# homeboard24.net
KiCad netlist of a schematic drawn in EAGLE
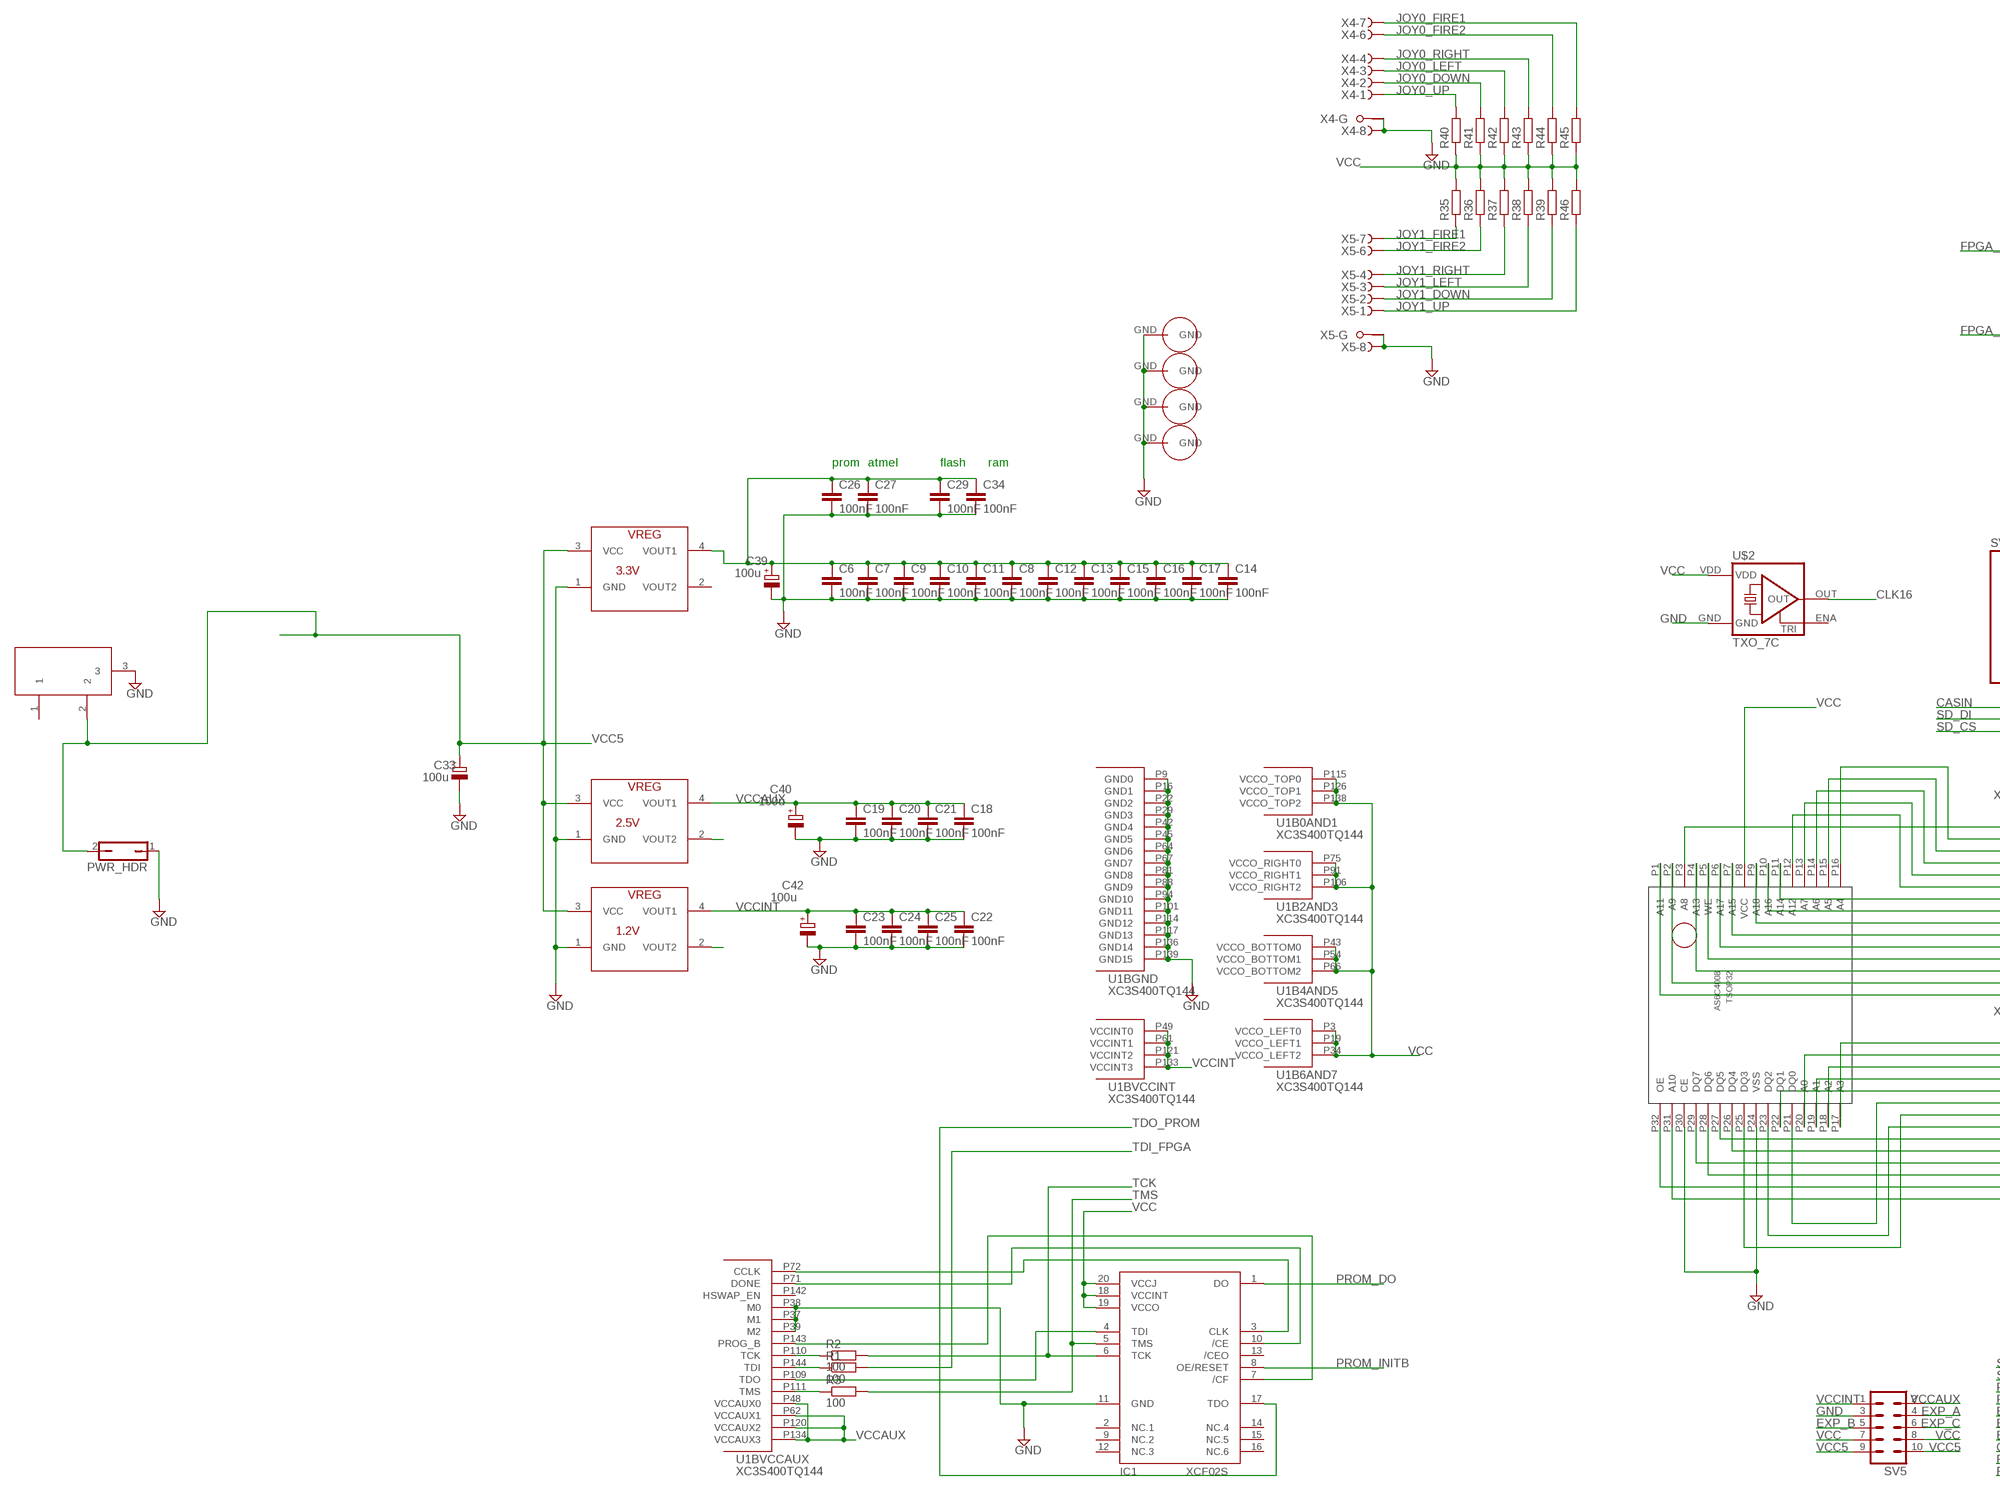
[diagram p0: schematic, sheet 1, part 1 of 3]
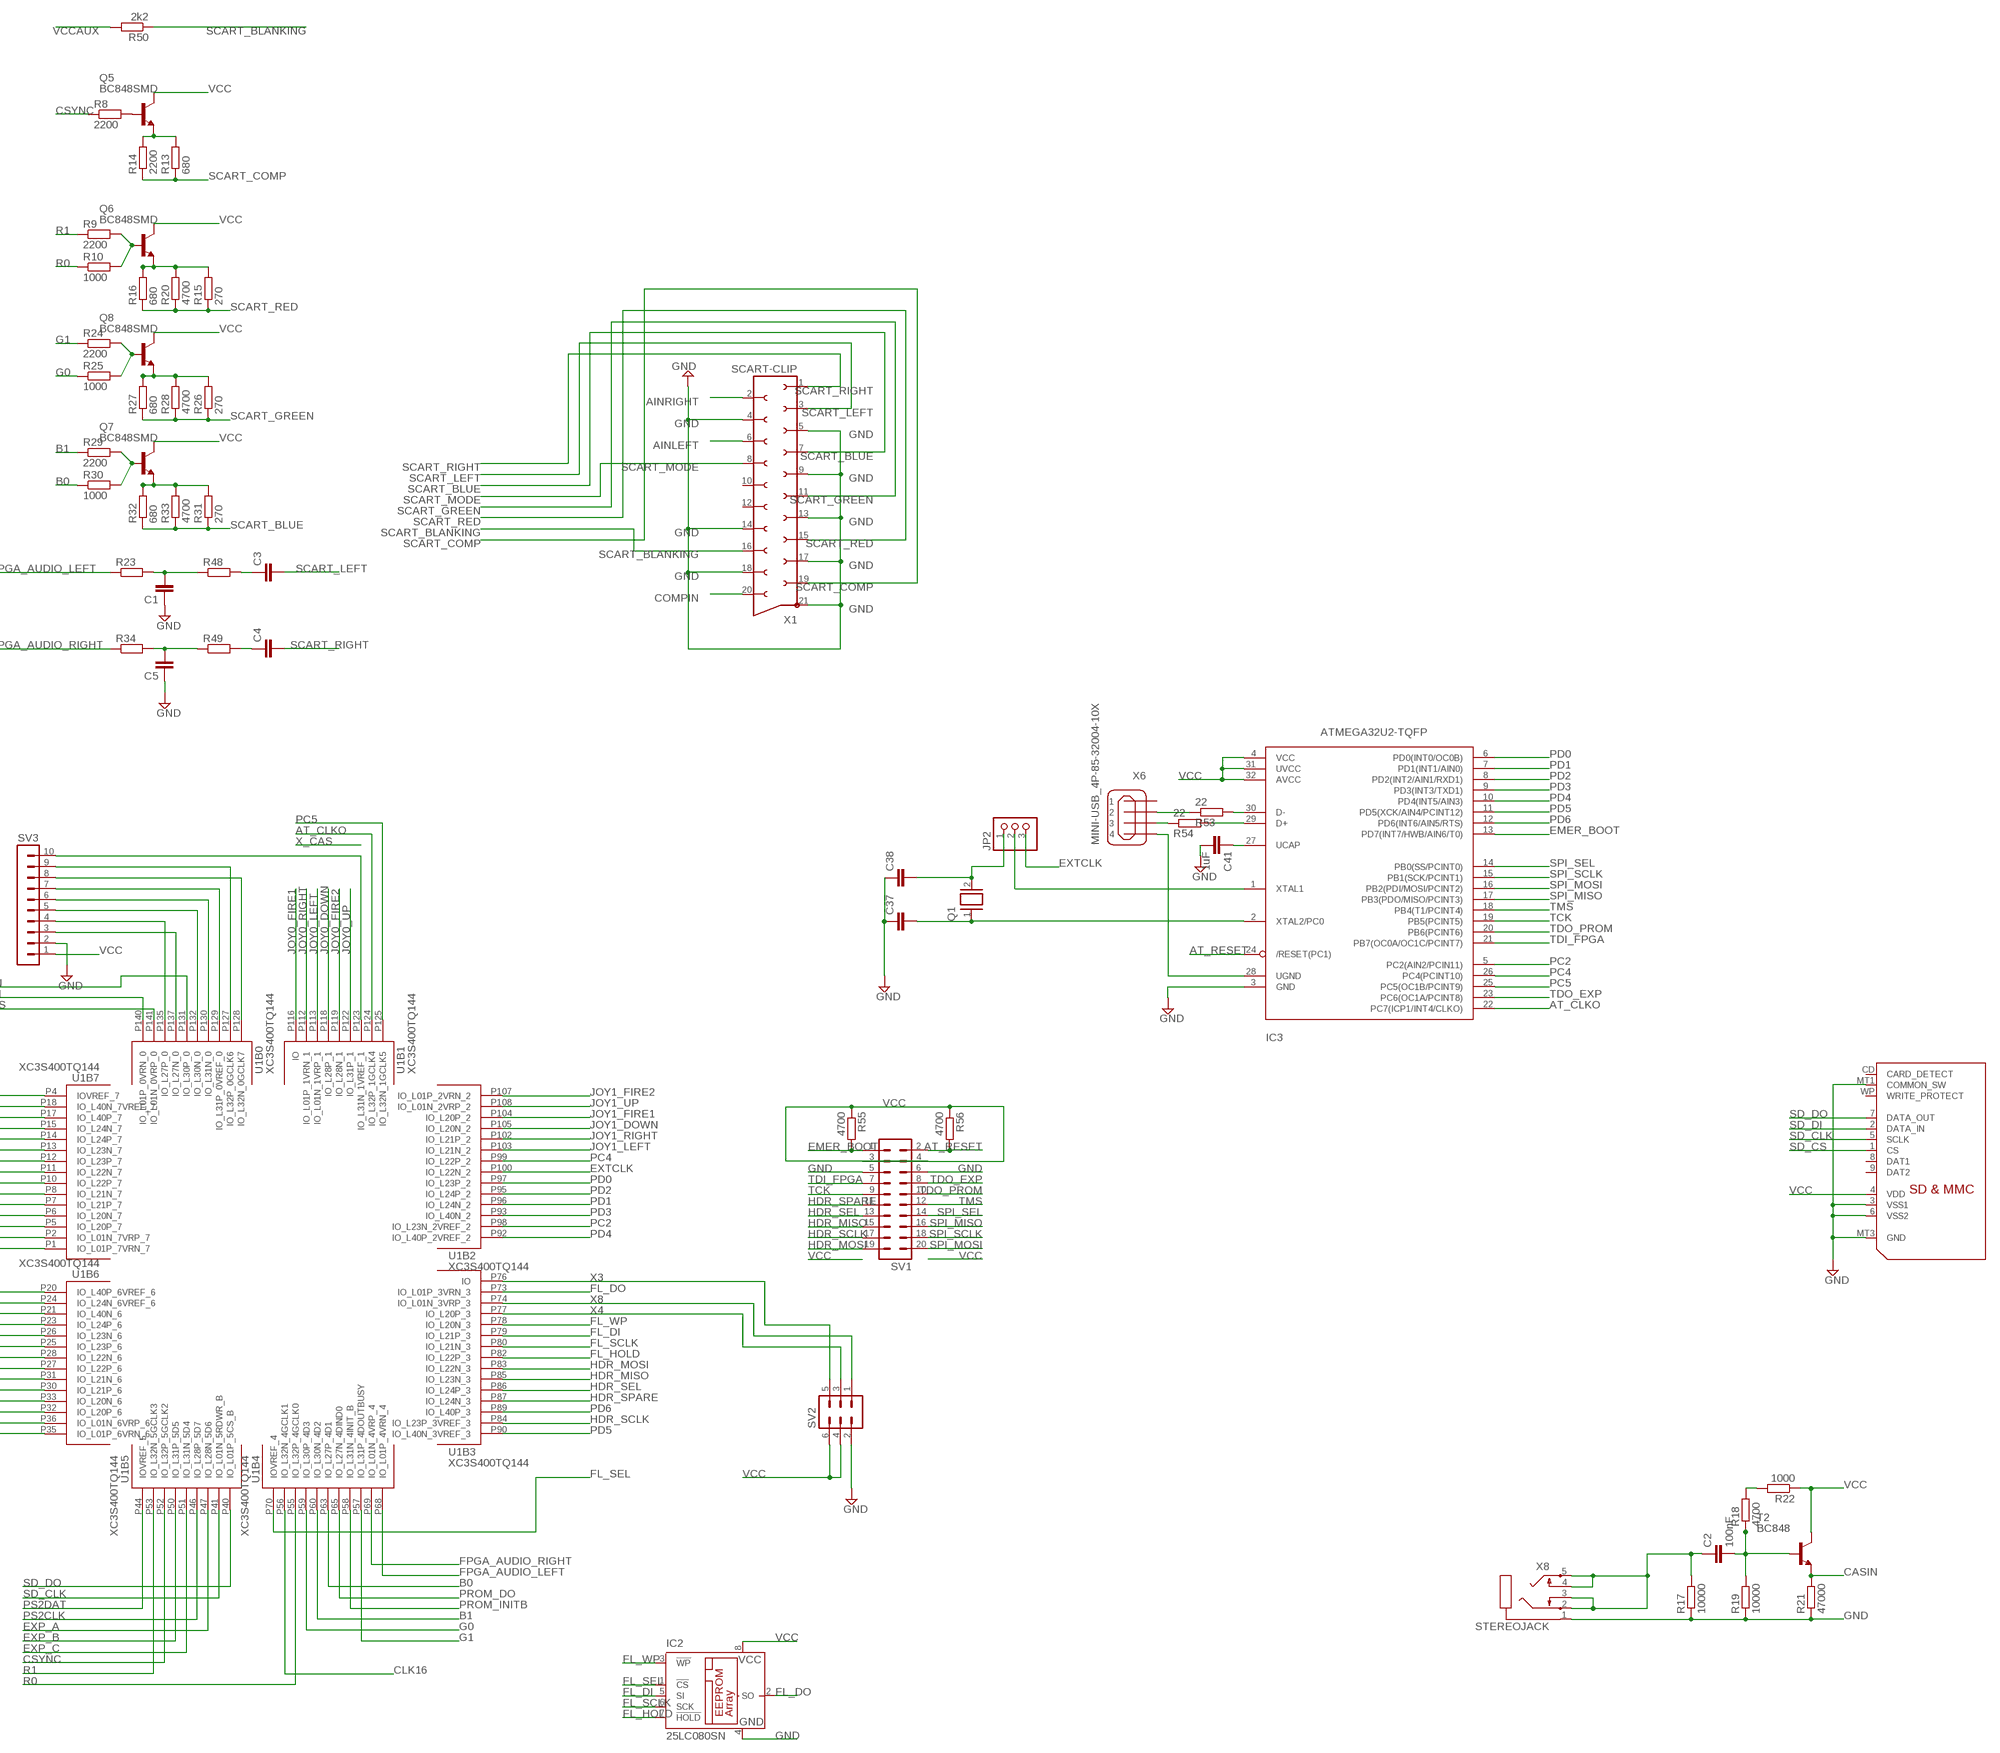
[diagram p1: schematic, sheet 1, part 2 of 3]
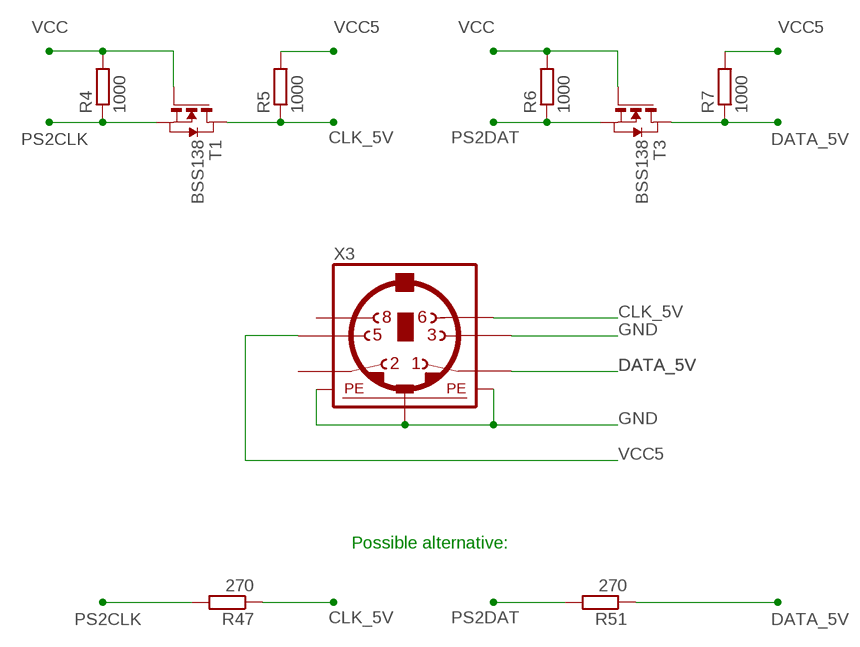
[diagram p2: schematic, sheet 1, part 3 of 3]

(export (version "E")
  (design (tool "Eeschema 10.0.6"))
  (components
    (comp (ref "C1")
      (value "C-EUC0603")
      (footprint "eagle-import:C0603")
      (libsource (lib "eagle-import") (part "resistor_C-EUC0603"))
    )
    (comp (ref "C2")
      (value "100nF")
      (footprint "eagle-import:C0603")
      (libsource (lib "eagle-import") (part "resistor_C-EUC0603"))
    )
    (comp (ref "C3")
      (value "C-EUC0603")
      (footprint "eagle-import:C0603")
      (libsource (lib "eagle-import") (part "resistor_C-EUC0603"))
    )
    (comp (ref "C4")
      (value "C-EUC0603")
      (footprint "eagle-import:C0603")
      (libsource (lib "eagle-import") (part "resistor_C-EUC0603"))
    )
    (comp (ref "C5")
      (value "C-EUC0603")
      (footprint "eagle-import:C0603")
      (libsource (lib "eagle-import") (part "resistor_C-EUC0603"))
    )
    (comp (ref "C6")
      (value "100nF")
      (footprint "eagle-import:C0603")
      (libsource (lib "eagle-import") (part "C-EUC0603"))
    )
    (comp (ref "C7")
      (value "100nF")
      (footprint "eagle-import:C0603")
      (libsource (lib "eagle-import") (part "C-EUC0603"))
    )
    (comp (ref "C8")
      (value "100nF")
      (footprint "eagle-import:C0603")
      (libsource (lib "eagle-import") (part "C-EUC0603"))
    )
    (comp (ref "C9")
      (value "100nF")
      (footprint "eagle-import:C0603")
      (libsource (lib "eagle-import") (part "C-EUC0603"))
    )
    (comp (ref "C10")
      (value "100nF")
      (footprint "eagle-import:C0603")
      (libsource (lib "eagle-import") (part "C-EUC0603"))
    )
    (comp (ref "C11")
      (value "100nF")
      (footprint "eagle-import:C0603")
      (libsource (lib "eagle-import") (part "C-EUC0603"))
    )
    (comp (ref "C12")
      (value "100nF")
      (footprint "eagle-import:C0603")
      (libsource (lib "eagle-import") (part "C-EUC0603"))
    )
    (comp (ref "C13")
      (value "100nF")
      (footprint "eagle-import:C0603")
      (libsource (lib "eagle-import") (part "C-EUC0603"))
    )
    (comp (ref "C14")
      (value "100nF")
      (footprint "eagle-import:C0603")
      (libsource (lib "eagle-import") (part "C-EUC0603"))
    )
    (comp (ref "C15")
      (value "100nF")
      (footprint "eagle-import:C0603")
      (libsource (lib "eagle-import") (part "C-EUC0603"))
    )
    (comp (ref "C16")
      (value "100nF")
      (footprint "eagle-import:C0603")
      (libsource (lib "eagle-import") (part "C-EUC0603"))
    )
    (comp (ref "C17")
      (value "100nF")
      (footprint "eagle-import:C0603")
      (libsource (lib "eagle-import") (part "C-EUC0603"))
    )
    (comp (ref "C18")
      (value "100nF")
      (footprint "eagle-import:C0603")
      (libsource (lib "eagle-import") (part "C-EUC0603"))
    )
    (comp (ref "C19")
      (value "100nF")
      (footprint "eagle-import:C0603")
      (libsource (lib "eagle-import") (part "C-EUC0603"))
    )
    (comp (ref "C20")
      (value "100nF")
      (footprint "eagle-import:C0603")
      (libsource (lib "eagle-import") (part "C-EUC0603"))
    )
    (comp (ref "C21")
      (value "100nF")
      (footprint "eagle-import:C0603")
      (libsource (lib "eagle-import") (part "C-EUC0603"))
    )
    (comp (ref "C22")
      (value "100nF")
      (footprint "eagle-import:C0603")
      (libsource (lib "eagle-import") (part "C-EUC0603"))
    )
    (comp (ref "C23")
      (value "100nF")
      (footprint "eagle-import:C0603")
      (libsource (lib "eagle-import") (part "C-EUC0603"))
    )
    (comp (ref "C24")
      (value "100nF")
      (footprint "eagle-import:C0603")
      (libsource (lib "eagle-import") (part "C-EUC0603"))
    )
    (comp (ref "C25")
      (value "100nF")
      (footprint "eagle-import:C0603")
      (libsource (lib "eagle-import") (part "C-EUC0603"))
    )
    (comp (ref "C26")
      (value "100nF")
      (footprint "eagle-import:C0603")
      (libsource (lib "eagle-import") (part "C-EUC0603"))
    )
    (comp (ref "C27")
      (value "100nF")
      (footprint "eagle-import:C0603")
      (libsource (lib "eagle-import") (part "C-EUC0603"))
    )
    (comp (ref "C29")
      (value "100nF")
      (footprint "eagle-import:C0603")
      (libsource (lib "eagle-import") (part "C-EUC0603"))
    )
    (comp (ref "C33")
      (value "100u")
      (footprint "eagle-import:PANASONIC_D")
      (libsource (lib "eagle-import") (part "CPOL-EUD"))
    )
    (comp (ref "C34")
      (value "100nF")
      (footprint "eagle-import:C0603")
      (libsource (lib "eagle-import") (part "C-EUC0603"))
    )
    (comp (ref "C37")
      (value "C-EUC0805")
      (footprint "eagle-import:C0805")
      (libsource (lib "eagle-import") (part "C-EUC0805"))
    )
    (comp (ref "C38")
      (value "C-EUC0805")
      (footprint "eagle-import:C0805")
      (libsource (lib "eagle-import") (part "C-EUC0805"))
    )
    (comp (ref "C39")
      (value "100u")
      (footprint "eagle-import:PANASONIC_D")
      (libsource (lib "eagle-import") (part "CPOL-EUD"))
    )
    (comp (ref "C40")
      (value "100u")
      (footprint "eagle-import:PANASONIC_D")
      (libsource (lib "eagle-import") (part "CPOL-EUD"))
    )
    (comp (ref "C41")
      (value "1uF")
      (footprint "eagle-import:C0805")
      (libsource (lib "eagle-import") (part "C-EUC0805"))
    )
    (comp (ref "C42")
      (value "100u")
      (footprint "eagle-import:PANASONIC_D")
      (libsource (lib "eagle-import") (part "CPOL-EUD"))
    )
    (comp (ref "IC1")
      (value "XCF02S")
      (footprint "eagle-import:VO20")
      (libsource (lib "eagle-import") (part "XCF02S"))
    )
    (comp (ref "IC2")
      (value "25LC080SN")
      (footprint "eagle-import:SO-08")
      (fields (field (name "MF") "MICROCHIP") (field (name "MPN") "25LC080/SN"))
      (libsource (lib "eagle-import") (part "25SNLC080"))
    )
    (comp (ref "IC3")
      (value "ATMEGA32U2-TQFP")
      (footprint "eagle-import:TQFP32-08")
      (libsource (lib "eagle-import") (part "ATMEGA32U2-TQFP"))
    )
    (comp (ref "JP2")
      (value "PINHD-1X3")
      (footprint "eagle-import:1X03")
      (libsource (lib "eagle-import") (part "PINHD-1X3"))
    )
    (comp (ref "PWR_HDR")
      (value "JP1Q")
      (footprint "eagle-import:JP1")
      (libsource (lib "eagle-import") (part "JP1Q"))
    )
    (comp (ref "Q1")
      (value "XTAL/S")
      (footprint "eagle-import:QS")
      (libsource (lib "eagle-import") (part "XTAL/S"))
    )
    (comp (ref "Q5")
      (value "BC848SMD")
      (footprint "eagle-import:SOT23")
      (libsource (lib "eagle-import") (part "BC848SMD"))
    )
    (comp (ref "Q6")
      (value "BC848SMD")
      (footprint "eagle-import:SOT23")
      (libsource (lib "eagle-import") (part "BC848SMD"))
    )
    (comp (ref "Q7")
      (value "BC848SMD")
      (footprint "eagle-import:SOT23")
      (libsource (lib "eagle-import") (part "BC848SMD"))
    )
    (comp (ref "Q8")
      (value "BC848SMD")
      (footprint "eagle-import:SOT23")
      (libsource (lib "eagle-import") (part "BC848SMD"))
    )
    (comp (ref "R1")
      (value "100")
      (footprint "eagle-import:R0805")
      (libsource (lib "eagle-import") (part "R-EU_R0805"))
    )
    (comp (ref "R2")
      (value "100")
      (footprint "eagle-import:R0805")
      (libsource (lib "eagle-import") (part "R-EU_R0805"))
    )
    (comp (ref "R3")
      (value "100")
      (footprint "eagle-import:R0805")
      (libsource (lib "eagle-import") (part "R-EU_R0805"))
    )
    (comp (ref "R4")
      (value "1000")
      (footprint "eagle-import:R0805")
      (libsource (lib "eagle-import") (part "R-EU_R0805"))
    )
    (comp (ref "R5")
      (value "1000")
      (footprint "eagle-import:R0805")
      (libsource (lib "eagle-import") (part "R-EU_R0805"))
    )
    (comp (ref "R6")
      (value "1000")
      (footprint "eagle-import:R0805")
      (libsource (lib "eagle-import") (part "R-EU_R0805"))
    )
    (comp (ref "R7")
      (value "1000")
      (footprint "eagle-import:R0805")
      (libsource (lib "eagle-import") (part "R-EU_R0805"))
    )
    (comp (ref "R8")
      (value "2200")
      (footprint "eagle-import:R0805")
      (libsource (lib "eagle-import") (part "R-EU_R0805"))
    )
    (comp (ref "R9")
      (value "2200")
      (footprint "eagle-import:R0805")
      (libsource (lib "eagle-import") (part "R-EU_R0805"))
    )
    (comp (ref "R10")
      (value "1000")
      (footprint "eagle-import:R0805")
      (libsource (lib "eagle-import") (part "R-EU_R0805"))
    )
    (comp (ref "R13")
      (value "680")
      (footprint "eagle-import:R0805")
      (libsource (lib "eagle-import") (part "R-EU_R0805"))
    )
    (comp (ref "R14")
      (value "2200")
      (footprint "eagle-import:R0805")
      (libsource (lib "eagle-import") (part "R-EU_R0805"))
    )
    (comp (ref "R15")
      (value "270")
      (footprint "eagle-import:R0805")
      (libsource (lib "eagle-import") (part "R-EU_R0805"))
    )
    (comp (ref "R16")
      (value "680")
      (footprint "eagle-import:R0805")
      (libsource (lib "eagle-import") (part "R-EU_R0805"))
    )
    (comp (ref "R17")
      (value "10000")
      (footprint "eagle-import:R0805")
      (libsource (lib "eagle-import") (part "R-EU_R0805"))
    )
    (comp (ref "R18")
      (value "4700")
      (footprint "eagle-import:R0805")
      (libsource (lib "eagle-import") (part "R-EU_R0805"))
    )
    (comp (ref "R19")
      (value "10000")
      (footprint "eagle-import:R0805")
      (libsource (lib "eagle-import") (part "R-EU_R0805"))
    )
    (comp (ref "R20")
      (value "4700")
      (footprint "eagle-import:R0805")
      (libsource (lib "eagle-import") (part "R-EU_R0805"))
    )
    (comp (ref "R21")
      (value "47000")
      (footprint "eagle-import:R0805")
      (libsource (lib "eagle-import") (part "R-EU_R0805"))
    )
    (comp (ref "R22")
      (value "1000")
      (footprint "eagle-import:R0805")
      (libsource (lib "eagle-import") (part "R-EU_R0805"))
    )
    (comp (ref "R23")
      (value "R-EU_M0805")
      (footprint "eagle-import:M0805")
      (libsource (lib "eagle-import") (part "resistor_R-EU_M0805"))
    )
    (comp (ref "R24")
      (value "2200")
      (footprint "eagle-import:R0805")
      (libsource (lib "eagle-import") (part "R-EU_R0805"))
    )
    (comp (ref "R25")
      (value "1000")
      (footprint "eagle-import:R0805")
      (libsource (lib "eagle-import") (part "R-EU_R0805"))
    )
    (comp (ref "R26")
      (value "270")
      (footprint "eagle-import:R0805")
      (libsource (lib "eagle-import") (part "R-EU_R0805"))
    )
    (comp (ref "R27")
      (value "680")
      (footprint "eagle-import:R0805")
      (libsource (lib "eagle-import") (part "R-EU_R0805"))
    )
    (comp (ref "R28")
      (value "4700")
      (footprint "eagle-import:R0805")
      (libsource (lib "eagle-import") (part "R-EU_R0805"))
    )
    (comp (ref "R29")
      (value "2200")
      (footprint "eagle-import:R0805")
      (libsource (lib "eagle-import") (part "R-EU_R0805"))
    )
    (comp (ref "R30")
      (value "1000")
      (footprint "eagle-import:R0805")
      (libsource (lib "eagle-import") (part "R-EU_R0805"))
    )
    (comp (ref "R31")
      (value "270")
      (footprint "eagle-import:R0805")
      (libsource (lib "eagle-import") (part "R-EU_R0805"))
    )
    (comp (ref "R32")
      (value "680")
      (footprint "eagle-import:R0805")
      (libsource (lib "eagle-import") (part "R-EU_R0805"))
    )
    (comp (ref "R33")
      (value "4700")
      (footprint "eagle-import:R0805")
      (libsource (lib "eagle-import") (part "R-EU_R0805"))
    )
    (comp (ref "R34")
      (value "R-EU_M0805")
      (footprint "eagle-import:M0805")
      (libsource (lib "eagle-import") (part "resistor_R-EU_M0805"))
    )
    (comp (ref "R35")
      (value "R-EU_M0805")
      (footprint "eagle-import:M0805")
      (libsource (lib "eagle-import") (part "resistor_R-EU_M0805"))
    )
    (comp (ref "R36")
      (value "R-EU_M0805")
      (footprint "eagle-import:M0805")
      (libsource (lib "eagle-import") (part "resistor_R-EU_M0805"))
    )
    (comp (ref "R37")
      (value "R-EU_M0805")
      (footprint "eagle-import:M0805")
      (libsource (lib "eagle-import") (part "resistor_R-EU_M0805"))
    )
    (comp (ref "R38")
      (value "R-EU_M0805")
      (footprint "eagle-import:M0805")
      (libsource (lib "eagle-import") (part "resistor_R-EU_M0805"))
    )
    (comp (ref "R39")
      (value "R-EU_M0805")
      (footprint "eagle-import:M0805")
      (libsource (lib "eagle-import") (part "resistor_R-EU_M0805"))
    )
    (comp (ref "R40")
      (value "R-EU_M0805")
      (footprint "eagle-import:M0805")
      (libsource (lib "eagle-import") (part "resistor_R-EU_M0805"))
    )
    (comp (ref "R41")
      (value "R-EU_M0805")
      (footprint "eagle-import:M0805")
      (libsource (lib "eagle-import") (part "resistor_R-EU_M0805"))
    )
    (comp (ref "R42")
      (value "R-EU_M0805")
      (footprint "eagle-import:M0805")
      (libsource (lib "eagle-import") (part "resistor_R-EU_M0805"))
    )
    (comp (ref "R43")
      (value "R-EU_M0805")
      (footprint "eagle-import:M0805")
      (libsource (lib "eagle-import") (part "resistor_R-EU_M0805"))
    )
    (comp (ref "R44")
      (value "R-EU_M0805")
      (footprint "eagle-import:M0805")
      (libsource (lib "eagle-import") (part "resistor_R-EU_M0805"))
    )
    (comp (ref "R45")
      (value "R-EU_M0805")
      (footprint "eagle-import:M0805")
      (libsource (lib "eagle-import") (part "resistor_R-EU_M0805"))
    )
    (comp (ref "R46")
      (value "R-EU_M0805")
      (footprint "eagle-import:M0805")
      (libsource (lib "eagle-import") (part "resistor_R-EU_M0805"))
    )
    (comp (ref "R47")
      (value "270")
      (footprint "eagle-import:R0805")
      (libsource (lib "eagle-import") (part "R-EU_R0805"))
    )
    (comp (ref "R48")
      (value "R-EU_M0805")
      (footprint "eagle-import:M0805")
      (libsource (lib "eagle-import") (part "resistor_R-EU_M0805"))
    )
    (comp (ref "R49")
      (value "R-EU_M0805")
      (footprint "eagle-import:M0805")
      (libsource (lib "eagle-import") (part "resistor_R-EU_M0805"))
    )
    (comp (ref "R50")
      (value "2k2")
      (footprint "eagle-import:M0805")
      (libsource (lib "eagle-import") (part "resistor_R-EU_M0805"))
    )
    (comp (ref "R51")
      (value "270")
      (footprint "eagle-import:R0805")
      (libsource (lib "eagle-import") (part "R-EU_R0805"))
    )
    (comp (ref "R53")
      (value "22")
      (footprint "eagle-import:R0805")
      (libsource (lib "eagle-import") (part "R-EU_R0805"))
    )
    (comp (ref "R54")
      (value "22")
      (footprint "eagle-import:R0805")
      (libsource (lib "eagle-import") (part "R-EU_R0805"))
    )
    (comp (ref "R55")
      (value "4700")
      (footprint "eagle-import:R0805")
      (libsource (lib "eagle-import") (part "R-EU_R0805"))
    )
    (comp (ref "R56")
      (value "4700")
      (footprint "eagle-import:R0805")
      (libsource (lib "eagle-import") (part "R-EU_R0805"))
    )
    (comp (ref "REG1.2")
      (value "1.2V")
      (footprint "eagle-import:SOT223")
      (libsource (lib "eagle-import") (part "NX1117"))
    )
    (comp (ref "REG2.5")
      (value "2.5V")
      (footprint "eagle-import:SOT223")
      (libsource (lib "eagle-import") (part "NX1117"))
    )
    (comp (ref "SV1")
      (value "MA10-2")
      (footprint "eagle-import:MA10-2")
      (fields (field (name "OC_FARNELL") "unknown") (field (name "OC_NEWARK") "unknown"))
      (libsource (lib "eagle-import") (part "MA10-2"))
    )
    (comp (ref "SV2")
      (value "MA03-2")
      (footprint "eagle-import:MA03-2")
      (libsource (lib "eagle-import") (part "MA03-2"))
    )
    (comp (ref "SV3")
      (value "MA10-1")
      (footprint "eagle-import:MA10-1")
      (libsource (lib "eagle-import") (part "MA10-1"))
    )
    (comp (ref "SV5")
      (value "MA05-2")
      (footprint "eagle-import:MA05-2")
      (libsource (lib "eagle-import") (part "MA05-2"))
    )
    (comp (ref "T1")
      (value "BSS138")
      (footprint "eagle-import:SOT-23")
      (libsource (lib "eagle-import") (part "NMOSSOT23"))
    )
    (comp (ref "T2")
      (value "BC848")
      (footprint "eagle-import:SOT23")
      (libsource (lib "eagle-import") (part "BC848"))
    )
    (comp (ref "T3")
      (value "BSS138")
      (footprint "eagle-import:SOT-23")
      (libsource (lib "eagle-import") (part "NMOSSOT23"))
    )
    (comp (ref "U$1")
      (value "GNDHOLE")
      (footprint "eagle-import:GNDHOLE")
      (libsource (lib "eagle-import") (part "GNDHOLE"))
    )
    (comp (ref "U$2")
      (value "TXO_7C")
      (footprint "eagle-import:OSC_7C")
      (libsource (lib "eagle-import") (part "TXO_7C"))
    )
    (comp (ref "U$3")
      (value "SDMMCNOHOLE")
      (footprint "eagle-import:SDCARD-NOHOLE")
      (libsource (lib "eagle-import") (part "SDMMCNOHOLE"))
    )
    (comp (ref "U$4")
      (value "3.3V")
      (footprint "eagle-import:SOT223")
      (libsource (lib "eagle-import") (part "NX1117"))
    )
    (comp (ref "U$6")
      (value "AS6C4008")
      (footprint "eagle-import:TSOP32")
      (libsource (lib "eagle-import") (part "AS6C4008"))
    )
    (comp (ref "U$7")
      (value "GNDHOLE")
      (footprint "eagle-import:GNDHOLE")
      (libsource (lib "eagle-import") (part "GNDHOLE"))
    )
    (comp (ref "U$8")
      (value "GNDHOLE")
      (footprint "eagle-import:GNDHOLE")
      (libsource (lib "eagle-import") (part "GNDHOLE"))
    )
    (comp (ref "U$9")
      (value "GNDHOLE")
      (footprint "eagle-import:GNDHOLE")
      (libsource (lib "eagle-import") (part "GNDHOLE"))
    )
    (comp (ref "U1")
      (value "XC3S400TQ144")
      (footprint "eagle-import:TQ144")
      (libsource (lib "eagle-import") (part "XC3S400TQ144"))
    )
    (comp (ref "X1")
      (value "SCART-CLIP")
      (footprint "eagle-import:SCART-CLIP")
      (libsource (lib "eagle-import") (part "SCART-CLIP"))
    )
    (comp (ref "X3")
      (value "MINI_DIN_6")
      (footprint "eagle-import:M_DIN6")
      (libsource (lib "eagle-import") (part "MINI_DIN_6"))
    )
    (comp (ref "X4")
      (value "F09HPS")
      (footprint "eagle-import:F09HP")
      (libsource (lib "eagle-import") (part "F09HPS"))
    )
    (comp (ref "X5")
      (value "F09HPS")
      (footprint "eagle-import:F09HP")
      (libsource (lib "eagle-import") (part "F09HPS"))
    )
    (comp (ref "X6")
      (value "MINI-USB_4P-85-32004-10X")
      (footprint "eagle-import:85-32004-10X")
      (libsource (lib "eagle-import") (part "MINI-USB_4P-85-32004-10X"))
    )
    (comp (ref "X7")
      (value "DC21MMX")
      (footprint "eagle-import:DC-21MM")
      (libsource (lib "eagle-import") (part "DC21MMX"))
    )
    (comp (ref "X8")
      (value "STEREOJACK")
      (footprint "eagle-import:20-0137")
      (libsource (lib "eagle-import") (part "STEREOJACK"))
    )
  )
  (nets
    (net (code "1") (name "/1") (class "Default")
      (node (ref "X7") (pin "1") (pinfunction "1_1") (pintype "power_in"))
    )
    (net (code "2") (name "/AINLEFT") (class "Default")
      (node (ref "X1") (pin "6") (pinfunction "6_6") (pintype "passive"))
    )
    (net (code "3") (name "/AINRIGHT") (class "Default")
      (node (ref "X1") (pin "2") (pinfunction "2_2") (pintype "passive"))
    )
    (net (code "4") (name "/AT_CLKO") (class "Default")
      (node (ref "IC3") (pin "22") (pinfunction "PC7(ICP1/INT4/CLKO)_22") (pintype "bidirectional"))
      (node (ref "U1") (pin "P124") (pinfunction "IO_L32P_1GCLK4_P124") (pintype "bidirectional"))
    )
    (net (code "5") (name "/AT_RESET") (class "Default")
      (node (ref "IC3") (pin "24") (pinfunction "/RESET(PC1)_24") (pintype "bidirectional"))
      (node (ref "R56") (pin "2") (pinfunction "2_2") (pintype "passive"))
      (node (ref "SV1") (pin "2") (pinfunction "2_2") (pintype "passive"))
    )
    (net (code "6") (name "/B0") (class "Default")
      (node (ref "R30") (pin "1") (pinfunction "1_1") (pintype "passive"))
      (node (ref "U1") (pin "P63") (pinfunction "IO_L27P_4D1_P63") (pintype "bidirectional"))
    )
    (net (code "7") (name "/B1") (class "Default")
      (node (ref "R29") (pin "1") (pinfunction "1_1") (pintype "passive"))
      (node (ref "U1") (pin "P60") (pinfunction "IO_L30N_4D2_P60") (pintype "bidirectional"))
    )
    (net (code "8") (name "/CASIN") (class "Default")
      (node (ref "R21") (pin "2") (pinfunction "2_2") (pintype "passive"))
      (node (ref "T2") (pin "2") (pinfunction "E_2") (pintype "passive"))
      (node (ref "U1") (pin "P131") (pinfunction "IO_L30P_0_P131") (pintype "bidirectional"))
    )
    (net (code "9") (name "/CLK16") (class "Default")
      (node (ref "U$2") (pin "OUT") (pinfunction "OUT_OUT") (pintype "output"))
      (node (ref "U1") (pin "P56") (pinfunction "IO_L32N_4GCLK1_P56") (pintype "bidirectional"))
    )
    (net (code "10") (name "/CLK_5V") (class "Default")
      (node (ref "R47") (pin "1") (pinfunction "1_1") (pintype "passive"))
      (node (ref "R5") (pin "1") (pinfunction "1_1") (pintype "passive"))
      (node (ref "T1") (pin "1") (pinfunction "D_1") (pintype "passive"))
      (node (ref "X3") (pin "6") (pinfunction "6_6") (pintype "passive"))
    )
    (net (code "11") (name "/COMPIN") (class "Default")
      (node (ref "X1") (pin "20") (pinfunction "20_20") (pintype "passive"))
    )
    (net (code "12") (name "/CSYNC") (class "Default")
      (node (ref "R8") (pin "1") (pinfunction "1_1") (pintype "passive"))
      (node (ref "U1") (pin "P52") (pinfunction "IO_L32P_5GCLK2_P52") (pintype "bidirectional"))
    )
    (net (code "13") (name "/DATA_5V") (class "Default")
      (node (ref "R51") (pin "1") (pinfunction "1_1") (pintype "passive"))
      (node (ref "R7") (pin "1") (pinfunction "1_1") (pintype "passive"))
      (node (ref "T3") (pin "1") (pinfunction "D_1") (pintype "passive"))
      (node (ref "X3") (pin "1") (pinfunction "1_1") (pintype "passive"))
    )
    (net (code "14") (name "/EMER_BOOT") (class "Default")
      (node (ref "IC3") (pin "13") (pinfunction "PD7(INT7/HWB/AIN6/T0)_13") (pintype "bidirectional"))
      (node (ref "R55") (pin "2") (pinfunction "2_2") (pintype "passive"))
      (node (ref "SV1") (pin "1") (pinfunction "1_1") (pintype "passive"))
    )
    (net (code "15") (name "/EXP_A") (class "Default")
      (node (ref "SV5") (pin "4") (pinfunction "4_4") (pintype "passive"))
      (node (ref "U1") (pin "P47") (pinfunction "IO_L28N_5D6_P47") (pintype "bidirectional"))
    )
    (net (code "16") (name "/EXP_B") (class "Default")
      (node (ref "SV5") (pin "5") (pinfunction "5_5") (pintype "passive"))
      (node (ref "U1") (pin "P50") (pinfunction "IO_L31P_5D5_P50") (pintype "bidirectional"))
    )
    (net (code "17") (name "/EXP_C") (class "Default")
      (node (ref "SV5") (pin "6") (pinfunction "6_6") (pintype "passive"))
      (node (ref "U1") (pin "P51") (pinfunction "IO_L31N_5D4_P51") (pintype "bidirectional"))
    )
    (net (code "18") (name "/EXTCLK") (class "Default")
      (node (ref "JP2") (pin "3") (pinfunction "3_3") (pintype "passive"))
      (node (ref "U1") (pin "P100") (pinfunction "IO_L22N_2_P100") (pintype "bidirectional"))
    )
    (net (code "19") (name "/FL_DI") (class "Default")
      (node (ref "IC2") (pin "5") (pinfunction "SI_5") (pintype "input"))
      (node (ref "U1") (pin "P79") (pinfunction "IO_L21P_3_P79") (pintype "bidirectional"))
    )
    (net (code "20") (name "/FL_DO") (class "Default")
      (node (ref "IC2") (pin "2") (pinfunction "SO_2") (pintype "bidirectional"))
      (node (ref "U1") (pin "P73") (pinfunction "IO_L01P_3VRN_3_P73") (pintype "bidirectional"))
    )
    (net (code "21") (name "/FL_HOLD") (class "Default")
      (node (ref "IC2") (pin "7") (pinfunction "~{HOLD}_7") (pintype "input"))
      (node (ref "U1") (pin "P82") (pinfunction "IO_L22P_3_P82") (pintype "bidirectional"))
    )
    (net (code "22") (name "/FL_SCLK") (class "Default")
      (node (ref "IC2") (pin "6") (pinfunction "SCK_6") (pintype "input"))
      (node (ref "U1") (pin "P80") (pinfunction "IO_L21N_3_P80") (pintype "bidirectional"))
    )
    (net (code "23") (name "/FL_SEL") (class "Default")
      (node (ref "IC2") (pin "1") (pinfunction "~{CS}_1") (pintype "input"))
      (node (ref "U1") (pin "P70") (pinfunction "IOVREF_4_P70") (pintype "bidirectional"))
    )
    (net (code "24") (name "/FL_WP") (class "Default")
      (node (ref "IC2") (pin "3") (pinfunction "~{WP}_3") (pintype "input"))
      (node (ref "U1") (pin "P78") (pinfunction "IO_L20N_3_P78") (pintype "bidirectional"))
    )
    (net (code "25") (name "/FPGA_AUDIO_LEFT") (class "Default")
      (node (ref "R23") (pin "1") (pinfunction "1_1") (pintype "passive"))
      (node (ref "U1") (pin "P68") (pinfunction "IO_L01P_4VRN_4_P68") (pintype "bidirectional"))
    )
    (net (code "26") (name "/FPGA_AUDIO_RIGHT") (class "Default")
      (node (ref "R34") (pin "1") (pinfunction "1_1") (pintype "passive"))
      (node (ref "U1") (pin "P69") (pinfunction "IO_L01N_4VRP_4_P69") (pintype "bidirectional"))
    )
    (net (code "27") (name "/G0") (class "Default")
      (node (ref "R25") (pin "1") (pinfunction "1_1") (pintype "passive"))
      (node (ref "U1") (pin "P59") (pinfunction "IO_L30P_4D3_P59") (pintype "bidirectional"))
    )
    (net (code "28") (name "/G1") (class "Default")
      (node (ref "R24") (pin "1") (pinfunction "1_1") (pintype "passive"))
      (node (ref "U1") (pin "P57") (pinfunction "IO_L31P_4DOUTBUSY_P57") (pintype "bidirectional"))
    )
    (net (code "29") (name "/HDR_MISO") (class "Default")
      (node (ref "SV1") (pin "15") (pinfunction "15_15") (pintype "passive"))
      (node (ref "U1") (pin "P85") (pinfunction "IO_L23N_3_P85") (pintype "bidirectional"))
    )
    (net (code "30") (name "/HDR_MOSI") (class "Default")
      (node (ref "SV1") (pin "19") (pinfunction "19_19") (pintype "passive"))
      (node (ref "U1") (pin "P83") (pinfunction "IO_L22N_3_P83") (pintype "bidirectional"))
    )
    (net (code "31") (name "/HDR_SCLK") (class "Default")
      (node (ref "SV1") (pin "17") (pinfunction "17_17") (pintype "passive"))
      (node (ref "U1") (pin "P84") (pinfunction "IO_L23P_3VREF_3_P84") (pintype "bidirectional"))
    )
    (net (code "32") (name "/HDR_SEL") (class "Default")
      (node (ref "SV1") (pin "13") (pinfunction "13_13") (pintype "passive"))
      (node (ref "U1") (pin "P86") (pinfunction "IO_L24P_3_P86") (pintype "bidirectional"))
    )
    (net (code "33") (name "/HDR_SPARE") (class "Default")
      (node (ref "SV1") (pin "11") (pinfunction "11_11") (pintype "passive"))
      (node (ref "U1") (pin "P87") (pinfunction "IO_L24N_3_P87") (pintype "bidirectional"))
    )
    (net (code "34") (name "/JOY0_DOWN") (class "Default")
      (node (ref "R41") (pin "2") (pinfunction "2_2") (pintype "passive"))
      (node (ref "U1") (pin "P118") (pinfunction "IO_L28P_1_P118") (pintype "bidirectional"))
      (node (ref "X4") (pin "2") (pinfunction "F_2") (pintype "passive"))
    )
    (net (code "35") (name "/JOY0_FIRE1") (class "Default")
      (node (ref "R45") (pin "2") (pinfunction "2_2") (pintype "passive"))
      (node (ref "U1") (pin "P116") (pinfunction "IO_P116") (pintype "bidirectional"))
      (node (ref "X4") (pin "7") (pinfunction "F_7") (pintype "passive"))
    )
    (net (code "36") (name "/JOY0_FIRE2") (class "Default")
      (node (ref "R44") (pin "2") (pinfunction "2_2") (pintype "passive"))
      (node (ref "U1") (pin "P119") (pinfunction "IO_L28N_1_P119") (pintype "bidirectional"))
      (node (ref "X4") (pin "6") (pinfunction "F_6") (pintype "passive"))
    )
    (net (code "37") (name "/JOY0_LEFT") (class "Default")
      (node (ref "R42") (pin "2") (pinfunction "2_2") (pintype "passive"))
      (node (ref "U1") (pin "P113") (pinfunction "IO_L01N_1VRP_1_P113") (pintype "bidirectional"))
      (node (ref "X4") (pin "3") (pinfunction "F_3") (pintype "passive"))
    )
    (net (code "38") (name "/JOY0_RIGHT") (class "Default")
      (node (ref "R43") (pin "2") (pinfunction "2_2") (pintype "passive"))
      (node (ref "U1") (pin "P112") (pinfunction "IO_L01P_1VRN_1_P112") (pintype "bidirectional"))
      (node (ref "X4") (pin "4") (pinfunction "F_4") (pintype "passive"))
    )
    (net (code "39") (name "/JOY0_UP") (class "Default")
      (node (ref "R40") (pin "2") (pinfunction "2_2") (pintype "passive"))
      (node (ref "U1") (pin "P122") (pinfunction "IO_L31P_1_P122") (pintype "bidirectional"))
      (node (ref "X4") (pin "1") (pinfunction "F_1") (pintype "passive"))
    )
    (net (code "40") (name "/JOY1_DOWN") (class "Default")
      (node (ref "R39") (pin "1") (pinfunction "1_1") (pintype "passive"))
      (node (ref "U1") (pin "P105") (pinfunction "IO_L20N_2_P105") (pintype "bidirectional"))
      (node (ref "X5") (pin "2") (pinfunction "F_2") (pintype "passive"))
    )
    (net (code "41") (name "/JOY1_FIRE1") (class "Default")
      (node (ref "R35") (pin "1") (pinfunction "1_1") (pintype "passive"))
      (node (ref "U1") (pin "P104") (pinfunction "IO_L20P_2_P104") (pintype "bidirectional"))
      (node (ref "X5") (pin "7") (pinfunction "F_7") (pintype "passive"))
    )
    (net (code "42") (name "/JOY1_FIRE2") (class "Default")
      (node (ref "R36") (pin "1") (pinfunction "1_1") (pintype "passive"))
      (node (ref "U1") (pin "P107") (pinfunction "IO_L01P_2VRN_2_P107") (pintype "bidirectional"))
      (node (ref "X5") (pin "6") (pinfunction "F_6") (pintype "passive"))
    )
    (net (code "43") (name "/JOY1_LEFT") (class "Default")
      (node (ref "R38") (pin "1") (pinfunction "1_1") (pintype "passive"))
      (node (ref "U1") (pin "P103") (pinfunction "IO_L21N_2_P103") (pintype "bidirectional"))
      (node (ref "X5") (pin "3") (pinfunction "F_3") (pintype "passive"))
    )
    (net (code "44") (name "/JOY1_RIGHT") (class "Default")
      (node (ref "R37") (pin "1") (pinfunction "1_1") (pintype "passive"))
      (node (ref "U1") (pin "P102") (pinfunction "IO_L21P_2_P102") (pintype "bidirectional"))
      (node (ref "X5") (pin "4") (pinfunction "F_4") (pintype "passive"))
    )
    (net (code "45") (name "/JOY1_UP") (class "Default")
      (node (ref "R46") (pin "1") (pinfunction "1_1") (pintype "passive"))
      (node (ref "U1") (pin "P108") (pinfunction "IO_L01N_2VRP_2_P108") (pintype "bidirectional"))
      (node (ref "X5") (pin "1") (pinfunction "F_1") (pintype "passive"))
    )
    (net (code "46") (name "/PC2") (class "Default")
      (node (ref "IC3") (pin "5") (pinfunction "PC2(AIN2/PCIN11)_5") (pintype "bidirectional"))
      (node (ref "U1") (pin "P98") (pinfunction "IO_L23N_2VREF_2_P98") (pintype "bidirectional"))
    )
    (net (code "47") (name "/PC4") (class "Default")
      (node (ref "IC3") (pin "26") (pinfunction "PC4(PCINT10)_26") (pintype "bidirectional"))
      (node (ref "U1") (pin "P99") (pinfunction "IO_L22P_2_P99") (pintype "bidirectional"))
    )
    (net (code "48") (name "/PC5") (class "Default")
      (node (ref "IC3") (pin "25") (pinfunction "PC5(OC1B/PCINT9)_25") (pintype "bidirectional"))
      (node (ref "U1") (pin "P125") (pinfunction "IO_L32N_1GCLK5_P125") (pintype "bidirectional"))
    )
    (net (code "49") (name "/PD0") (class "Default")
      (node (ref "IC3") (pin "6") (pinfunction "PD0(INT0/OC0B)_6") (pintype "bidirectional"))
      (node (ref "U1") (pin "P97") (pinfunction "IO_L23P_2_P97") (pintype "bidirectional"))
    )
    (net (code "50") (name "/PD1") (class "Default")
      (node (ref "IC3") (pin "7") (pinfunction "PD1(INT1/AIN0)_7") (pintype "bidirectional"))
      (node (ref "U1") (pin "P96") (pinfunction "IO_L24N_2_P96") (pintype "bidirectional"))
    )
    (net (code "51") (name "/PD2") (class "Default")
      (node (ref "IC3") (pin "8") (pinfunction "PD2(INT2/AIN1/RXD1)_8") (pintype "bidirectional"))
      (node (ref "U1") (pin "P95") (pinfunction "IO_L24P_2_P95") (pintype "bidirectional"))
    )
    (net (code "52") (name "/PD3") (class "Default")
      (node (ref "IC3") (pin "9") (pinfunction "PD3(INT3/TXD1)_9") (pintype "bidirectional"))
      (node (ref "U1") (pin "P93") (pinfunction "IO_L40N_2_P93") (pintype "bidirectional"))
    )
    (net (code "53") (name "/PD4") (class "Default")
      (node (ref "IC3") (pin "10") (pinfunction "PD4(INT5/AIN3)_10") (pintype "bidirectional"))
      (node (ref "U1") (pin "P92") (pinfunction "IO_L40P_2VREF_2_P92") (pintype "bidirectional"))
    )
    (net (code "54") (name "/PD5") (class "Default")
      (node (ref "IC3") (pin "11") (pinfunction "PD5(XCK/AIN4/PCINT12)_11") (pintype "bidirectional"))
      (node (ref "U1") (pin "P90") (pinfunction "IO_L40N_3VREF_3_P90") (pintype "bidirectional"))
    )
    (net (code "55") (name "/PD6") (class "Default")
      (node (ref "IC3") (pin "12") (pinfunction "PD6(INT6/AIN5/RTS)_12") (pintype "bidirectional"))
      (node (ref "U1") (pin "P89") (pinfunction "IO_L40P_3_P89") (pintype "bidirectional"))
    )
    (net (code "56") (name "/PROM_DO") (class "Default")
      (node (ref "IC1") (pin "1") (pinfunction "DO_1") (pintype "bidirectional"))
      (node (ref "U1") (pin "P65") (pinfunction "IO_L27N_4DIND0_P65") (pintype "bidirectional"))
    )
    (net (code "57") (name "/PROM_INITB") (class "Default")
      (node (ref "IC1") (pin "8") (pinfunction "OE/RESET_8") (pintype "bidirectional"))
      (node (ref "U1") (pin "P58") (pinfunction "IO_L31N_4INIT_B_P58") (pintype "bidirectional"))
    )
    (net (code "58") (name "/PS2CLK") (class "Default")
      (node (ref "R4") (pin "1") (pinfunction "1_1") (pintype "passive"))
      (node (ref "R47") (pin "2") (pinfunction "2_2") (pintype "passive"))
      (node (ref "T1") (pin "2") (pinfunction "S_2") (pintype "passive"))
      (node (ref "U1") (pin "P46") (pinfunction "IO_L28P_5D7_P46") (pintype "bidirectional"))
    )
    (net (code "59") (name "/PS2DAT") (class "Default")
      (node (ref "R51") (pin "2") (pinfunction "2_2") (pintype "passive"))
      (node (ref "R6") (pin "1") (pinfunction "1_1") (pintype "passive"))
      (node (ref "T3") (pin "2") (pinfunction "S_2") (pintype "passive"))
      (node (ref "U1") (pin "P44") (pinfunction "IOVREF_5_P44") (pintype "bidirectional"))
    )
    (net (code "60") (name "/R0") (class "Default")
      (node (ref "R10") (pin "1") (pinfunction "1_1") (pintype "passive"))
      (node (ref "U1") (pin "P55") (pinfunction "IO_L32P_4GCLK0_P55") (pintype "bidirectional"))
    )
    (net (code "61") (name "/R1") (class "Default")
      (node (ref "R9") (pin "1") (pinfunction "1_1") (pintype "passive"))
      (node (ref "U1") (pin "P53") (pinfunction "IO_L32N_5GCLK3_P53") (pintype "bidirectional"))
    )
    (net (code "62") (name "/SCART_BLANKING") (class "Default")
      (node (ref "R50") (pin "1") (pinfunction "1_1") (pintype "passive"))
      (node (ref "X1") (pin "16") (pinfunction "16_16") (pintype "passive"))
    )
    (net (code "63") (name "/SCART_BLUE") (class "Default")
      (node (ref "R31") (pin "1") (pinfunction "1_1") (pintype "passive"))
      (node (ref "R32") (pin "1") (pinfunction "1_1") (pintype "passive"))
      (node (ref "R33") (pin "1") (pinfunction "1_1") (pintype "passive"))
      (node (ref "X1") (pin "7") (pinfunction "7_7") (pintype "passive"))
    )
    (net (code "64") (name "/SCART_COMP") (class "Default")
      (node (ref "R13") (pin "1") (pinfunction "1_1") (pintype "passive"))
      (node (ref "R14") (pin "1") (pinfunction "1_1") (pintype "passive"))
      (node (ref "X1") (pin "19") (pinfunction "19_19") (pintype "passive"))
    )
    (net (code "65") (name "/SCART_GREEN") (class "Default")
      (node (ref "R26") (pin "1") (pinfunction "1_1") (pintype "passive"))
      (node (ref "R27") (pin "1") (pinfunction "1_1") (pintype "passive"))
      (node (ref "R28") (pin "1") (pinfunction "1_1") (pintype "passive"))
      (node (ref "X1") (pin "11") (pinfunction "11_11") (pintype "passive"))
    )
    (net (code "66") (name "/SCART_LEFT") (class "Default")
      (node (ref "C3") (pin "2") (pinfunction "2_2") (pintype "passive"))
      (node (ref "X1") (pin "3") (pinfunction "3_3") (pintype "passive"))
    )
    (net (code "67") (name "/SCART_MODE") (class "Default")
      (node (ref "X1") (pin "8") (pinfunction "8_8") (pintype "passive"))
    )
    (net (code "68") (name "/SCART_RED") (class "Default")
      (node (ref "R15") (pin "1") (pinfunction "1_1") (pintype "passive"))
      (node (ref "R16") (pin "1") (pinfunction "1_1") (pintype "passive"))
      (node (ref "R20") (pin "1") (pinfunction "1_1") (pintype "passive"))
      (node (ref "X1") (pin "15") (pinfunction "15_15") (pintype "passive"))
    )
    (net (code "69") (name "/SCART_RIGHT") (class "Default")
      (node (ref "C4") (pin "2") (pinfunction "2_2") (pintype "passive"))
      (node (ref "X1") (pin "1") (pinfunction "1_1") (pintype "passive"))
    )
    (net (code "70") (name "/SD_CLK") (class "Default")
      (node (ref "U$3") (pin "5") (pinfunction "SCLK_5") (pintype "input"))
      (node (ref "U1") (pin "P41") (pinfunction "IO_L01N_5RDWR_B_P41") (pintype "bidirectional"))
    )
    (net (code "71") (name "/SD_CS") (class "Default")
      (node (ref "U$3") (pin "1") (pinfunction "CS_1") (pintype "input"))
      (node (ref "U1") (pin "P141") (pinfunction "IO_L01N_0VRP_0_P141") (pintype "bidirectional"))
    )
    (net (code "72") (name "/SD_DI") (class "Default")
      (node (ref "U$3") (pin "2") (pinfunction "DATA_IN_2") (pintype "input"))
      (node (ref "U1") (pin "P140") (pinfunction "IO_L01P_0VRN_0_P140") (pintype "bidirectional"))
    )
    (net (code "73") (name "/SD_DO") (class "Default")
      (node (ref "U$3") (pin "7") (pinfunction "DATA_OUT_7") (pintype "output"))
      (node (ref "U1") (pin "P40") (pinfunction "IO_L01P_5CS_B_P40") (pintype "bidirectional"))
    )
    (net (code "74") (name "/SPI_MISO") (class "Default")
      (node (ref "IC3") (pin "17") (pinfunction "PB3(PDO/MISO/PCINT3)_17") (pintype "bidirectional"))
      (node (ref "SV1") (pin "16") (pinfunction "16_16") (pintype "passive"))
    )
    (net (code "75") (name "/SPI_MOSI") (class "Default")
      (node (ref "IC3") (pin "16") (pinfunction "PB2(PDI/MOSI/PCINT2)_16") (pintype "bidirectional"))
      (node (ref "SV1") (pin "20") (pinfunction "20_20") (pintype "passive"))
    )
    (net (code "76") (name "/SPI_SCLK") (class "Default")
      (node (ref "IC3") (pin "15") (pinfunction "PB1(SCK/PCINT1)_15") (pintype "bidirectional"))
      (node (ref "SV1") (pin "18") (pinfunction "18_18") (pintype "passive"))
    )
    (net (code "77") (name "/SPI_SEL") (class "Default")
      (node (ref "IC3") (pin "14") (pinfunction "PB0(SS/PCINT0)_14") (pintype "bidirectional"))
      (node (ref "SV1") (pin "14") (pinfunction "14_14") (pintype "passive"))
    )
    (net (code "78") (name "/TCK") (class "Default")
      (node (ref "IC1") (pin "6") (pinfunction "TCK_6") (pintype "bidirectional"))
      (node (ref "IC3") (pin "19") (pinfunction "PB5(PCINT5)_19") (pintype "bidirectional"))
      (node (ref "R2") (pin "2") (pinfunction "2_2") (pintype "passive"))
      (node (ref "SV1") (pin "9") (pinfunction "9_9") (pintype "passive"))
    )
    (net (code "79") (name "/TDI_FPGA") (class "Default")
      (node (ref "IC3") (pin "21") (pinfunction "PB7(OC0A/OC1C/PCINT7)_21") (pintype "bidirectional"))
      (node (ref "R1") (pin "2") (pinfunction "2_2") (pintype "passive"))
      (node (ref "SV1") (pin "7") (pinfunction "7_7") (pintype "passive"))
    )
    (net (code "80") (name "/TDO_EXP") (class "Default")
      (node (ref "IC3") (pin "23") (pinfunction "PC6(OC1A/PCINT8)_23") (pintype "bidirectional"))
      (node (ref "SV1") (pin "8") (pinfunction "8_8") (pintype "passive"))
    )
    (net (code "81") (name "/TDO_PROM") (class "Default")
      (node (ref "IC1") (pin "17") (pinfunction "TDO_17") (pintype "bidirectional"))
      (node (ref "IC3") (pin "20") (pinfunction "PB6(PCINT6)_20") (pintype "bidirectional"))
      (node (ref "SV1") (pin "10") (pinfunction "10_10") (pintype "passive"))
    )
    (net (code "82") (name "/TMS") (class "Default")
      (node (ref "IC1") (pin "5") (pinfunction "TMS_5") (pintype "bidirectional"))
      (node (ref "IC3") (pin "18") (pinfunction "PB4(T1/PCINT4)_18") (pintype "bidirectional"))
      (node (ref "R3") (pin "2") (pinfunction "2_2") (pintype "passive"))
      (node (ref "SV1") (pin "12") (pinfunction "12_12") (pintype "passive"))
    )
    (net (code "83") (name "/VCC") (class "Default")
      (node (ref "C10") (pin "1") (pinfunction "1_1") (pintype "passive"))
      (node (ref "C11") (pin "1") (pinfunction "1_1") (pintype "passive"))
      (node (ref "C12") (pin "1") (pinfunction "1_1") (pintype "passive"))
      (node (ref "C13") (pin "1") (pinfunction "1_1") (pintype "passive"))
      (node (ref "C14") (pin "1") (pinfunction "1_1") (pintype "passive"))
      (node (ref "C15") (pin "1") (pinfunction "1_1") (pintype "passive"))
      (node (ref "C16") (pin "1") (pinfunction "1_1") (pintype "passive"))
      (node (ref "C17") (pin "1") (pinfunction "1_1") (pintype "passive"))
      (node (ref "C26") (pin "1") (pinfunction "1_1") (pintype "passive"))
      (node (ref "C27") (pin "1") (pinfunction "1_1") (pintype "passive"))
      (node (ref "C29") (pin "1") (pinfunction "1_1") (pintype "passive"))
      (node (ref "C34") (pin "1") (pinfunction "1_1") (pintype "passive"))
      (node (ref "C39") (pin "+") (pinfunction "+_+") (pintype "passive"))
      (node (ref "C6") (pin "1") (pinfunction "1_1") (pintype "passive"))
      (node (ref "C7") (pin "1") (pinfunction "1_1") (pintype "passive"))
      (node (ref "C8") (pin "1") (pinfunction "1_1") (pintype "passive"))
      (node (ref "C9") (pin "1") (pinfunction "1_1") (pintype "passive"))
      (node (ref "IC1") (pin "18") (pinfunction "VCCINT_18") (pintype "bidirectional"))
      (node (ref "IC1") (pin "19") (pinfunction "VCCO_19") (pintype "bidirectional"))
      (node (ref "IC1") (pin "20") (pinfunction "VCCJ_20") (pintype "bidirectional"))
      (node (ref "IC2") (pin "8") (pinfunction "VCC_8") (pintype "power_in"))
      (node (ref "IC3") (pin "31") (pinfunction "UVCC_31") (pintype "bidirectional"))
      (node (ref "IC3") (pin "32") (pinfunction "AVCC_32") (pintype "bidirectional"))
      (node (ref "IC3") (pin "4") (pinfunction "VCC_4") (pintype "bidirectional"))
      (node (ref "Q5") (pin "3") (pinfunction "C_3") (pintype "passive"))
      (node (ref "Q6") (pin "3") (pinfunction "C_3") (pintype "passive"))
      (node (ref "Q7") (pin "3") (pinfunction "C_3") (pintype "passive"))
      (node (ref "Q8") (pin "3") (pinfunction "C_3") (pintype "passive"))
      (node (ref "R22") (pin "1") (pinfunction "1_1") (pintype "passive"))
      (node (ref "R35") (pin "2") (pinfunction "2_2") (pintype "passive"))
      (node (ref "R36") (pin "2") (pinfunction "2_2") (pintype "passive"))
      (node (ref "R37") (pin "2") (pinfunction "2_2") (pintype "passive"))
      (node (ref "R38") (pin "2") (pinfunction "2_2") (pintype "passive"))
      (node (ref "R39") (pin "2") (pinfunction "2_2") (pintype "passive"))
      (node (ref "R4") (pin "2") (pinfunction "2_2") (pintype "passive"))
      (node (ref "R40") (pin "1") (pinfunction "1_1") (pintype "passive"))
      (node (ref "R41") (pin "1") (pinfunction "1_1") (pintype "passive"))
      (node (ref "R42") (pin "1") (pinfunction "1_1") (pintype "passive"))
      (node (ref "R43") (pin "1") (pinfunction "1_1") (pintype "passive"))
      (node (ref "R44") (pin "1") (pinfunction "1_1") (pintype "passive"))
      (node (ref "R45") (pin "1") (pinfunction "1_1") (pintype "passive"))
      (node (ref "R46") (pin "2") (pinfunction "2_2") (pintype "passive"))
      (node (ref "R55") (pin "1") (pinfunction "1_1") (pintype "passive"))
      (node (ref "R56") (pin "1") (pinfunction "1_1") (pintype "passive"))
      (node (ref "R6") (pin "2") (pinfunction "2_2") (pintype "passive"))
      (node (ref "SV1") (pin "3") (pinfunction "3_3") (pintype "passive"))
      (node (ref "SV1") (pin "4") (pinfunction "4_4") (pintype "passive"))
      (node (ref "SV2") (pin "4") (pinfunction "4_4") (pintype "passive"))
      (node (ref "SV2") (pin "6") (pinfunction "6_6") (pintype "passive"))
      (node (ref "SV3") (pin "1") (pinfunction "1_1") (pintype "passive"))
      (node (ref "SV5") (pin "7") (pinfunction "7_7") (pintype "passive"))
      (node (ref "SV5") (pin "8") (pinfunction "8_8") (pintype "passive"))
      (node (ref "T1") (pin "3") (pinfunction "G_3") (pintype "passive"))
      (node (ref "T2") (pin "3") (pinfunction "C_3") (pintype "passive"))
      (node (ref "T3") (pin "3") (pinfunction "G_3") (pintype "passive"))
      (node (ref "U$2") (pin "VDD") (pinfunction "VDD_VDD") (pintype "power_in"))
      (node (ref "U$3") (pin "4") (pinfunction "VDD_4") (pintype "power_in"))
      (node (ref "U$4") (pin "4") (pinfunction "VOUT1_4") (pintype "bidirectional"))
      (node (ref "U$6") (pin "P8") (pinfunction "VCC_P8") (pintype "bidirectional"))
      (node (ref "U1") (pin "P106") (pinfunction "VCCO_RIGHT2_P106") (pintype "passive"))
      (node (ref "U1") (pin "P115") (pinfunction "VCCO_TOP0_P115") (pintype "passive"))
      (node (ref "U1") (pin "P126") (pinfunction "VCCO_TOP1_P126") (pintype "passive"))
      (node (ref "U1") (pin "P138") (pinfunction "VCCO_TOP2_P138") (pintype "passive"))
      (node (ref "U1") (pin "P19") (pinfunction "VCCO_LEFT1_P19") (pintype "passive"))
      (node (ref "U1") (pin "P3") (pinfunction "VCCO_LEFT0_P3") (pintype "passive"))
      (node (ref "U1") (pin "P34") (pinfunction "VCCO_LEFT2_P34") (pintype "passive"))
      (node (ref "U1") (pin "P43") (pinfunction "VCCO_BOTTOM0_P43") (pintype "passive"))
      (node (ref "U1") (pin "P54") (pinfunction "VCCO_BOTTOM1_P54") (pintype "passive"))
      (node (ref "U1") (pin "P66") (pinfunction "VCCO_BOTTOM2_P66") (pintype "passive"))
      (node (ref "U1") (pin "P75") (pinfunction "VCCO_RIGHT0_P75") (pintype "passive"))
      (node (ref "U1") (pin "P91") (pinfunction "VCCO_RIGHT1_P91") (pintype "passive"))
    )
    (net (code "84") (name "/VCC5") (class "Default")
      (node (ref "C33") (pin "+") (pinfunction "+_+") (pintype "passive"))
      (node (ref "PWR_HDR") (pin "2") (pinfunction "2_2") (pintype "passive"))
      (node (ref "R5") (pin "2") (pinfunction "2_2") (pintype "passive"))
      (node (ref "R7") (pin "2") (pinfunction "2_2") (pintype "passive"))
      (node (ref "REG1.2") (pin "3") (pinfunction "VCC_3") (pintype "bidirectional"))
      (node (ref "REG2.5") (pin "3") (pinfunction "VCC_3") (pintype "bidirectional"))
      (node (ref "SV5") (pin "10") (pinfunction "10_10") (pintype "passive"))
      (node (ref "SV5") (pin "9") (pinfunction "9_9") (pintype "passive"))
      (node (ref "U$4") (pin "3") (pinfunction "VCC_3") (pintype "bidirectional"))
      (node (ref "X3") (pin "5") (pinfunction "5_5") (pintype "passive"))
      (node (ref "X7") (pin "2") (pinfunction "2_2") (pintype "power_in"))
    )
    (net (code "85") (name "/VCCAUX") (class "Default")
      (node (ref "C18") (pin "1") (pinfunction "1_1") (pintype "passive"))
      (node (ref "C19") (pin "1") (pinfunction "1_1") (pintype "passive"))
      (node (ref "C20") (pin "1") (pinfunction "1_1") (pintype "passive"))
      (node (ref "C21") (pin "1") (pinfunction "1_1") (pintype "passive"))
      (node (ref "C40") (pin "+") (pinfunction "+_+") (pintype "passive"))
      (node (ref "R50") (pin "2") (pinfunction "2_2") (pintype "passive"))
      (node (ref "REG2.5") (pin "4") (pinfunction "VOUT1_4") (pintype "bidirectional"))
      (node (ref "SV5") (pin "2") (pinfunction "2_2") (pintype "passive"))
      (node (ref "U1") (pin "P120") (pinfunction "VCCAUX2_P120") (pintype "passive"))
      (node (ref "U1") (pin "P134") (pinfunction "VCCAUX3_P134") (pintype "passive"))
      (node (ref "U1") (pin "P48") (pinfunction "VCCAUX0_P48") (pintype "passive"))
      (node (ref "U1") (pin "P62") (pinfunction "VCCAUX1_P62") (pintype "passive"))
    )
    (net (code "86") (name "/VCCINT") (class "Default")
      (node (ref "C22") (pin "1") (pinfunction "1_1") (pintype "passive"))
      (node (ref "C23") (pin "1") (pinfunction "1_1") (pintype "passive"))
      (node (ref "C24") (pin "1") (pinfunction "1_1") (pintype "passive"))
      (node (ref "C25") (pin "1") (pinfunction "1_1") (pintype "passive"))
      (node (ref "C42") (pin "+") (pinfunction "+_+") (pintype "passive"))
      (node (ref "REG1.2") (pin "4") (pinfunction "VOUT1_4") (pintype "bidirectional"))
      (node (ref "SV5") (pin "1") (pinfunction "1_1") (pintype "passive"))
      (node (ref "U1") (pin "P121") (pinfunction "VCCINT2_P121") (pintype "passive"))
      (node (ref "U1") (pin "P133") (pinfunction "VCCINT3_P133") (pintype "passive"))
      (node (ref "U1") (pin "P49") (pinfunction "VCCINT0_P49") (pintype "passive"))
      (node (ref "U1") (pin "P61") (pinfunction "VCCINT1_P61") (pintype "passive"))
    )
    (net (code "87") (name "/X3") (class "Default")
      (node (ref "SV2") (pin "5") (pinfunction "5_5") (pintype "passive"))
      (node (ref "U1") (pin "P76") (pinfunction "IO_P76") (pintype "bidirectional"))
    )
    (net (code "88") (name "/X4") (class "Default")
      (node (ref "SV2") (pin "3") (pinfunction "3_3") (pintype "passive"))
      (node (ref "U1") (pin "P77") (pinfunction "IO_L20P_3_P77") (pintype "bidirectional"))
    )
    (net (code "89") (name "/X8") (class "Default")
      (node (ref "SV2") (pin "1") (pinfunction "1_1") (pintype "passive"))
      (node (ref "U1") (pin "P74") (pinfunction "IO_L01N_3VRP_3_P74") (pintype "bidirectional"))
    )
    (net (code "91") (name "GND") (class "Default")
      (node (ref "C1") (pin "1") (pinfunction "1_1") (pintype "passive"))
      (node (ref "C10") (pin "2") (pinfunction "2_2") (pintype "passive"))
      (node (ref "C11") (pin "2") (pinfunction "2_2") (pintype "passive"))
      (node (ref "C12") (pin "2") (pinfunction "2_2") (pintype "passive"))
      (node (ref "C13") (pin "2") (pinfunction "2_2") (pintype "passive"))
      (node (ref "C14") (pin "2") (pinfunction "2_2") (pintype "passive"))
      (node (ref "C15") (pin "2") (pinfunction "2_2") (pintype "passive"))
      (node (ref "C16") (pin "2") (pinfunction "2_2") (pintype "passive"))
      (node (ref "C17") (pin "2") (pinfunction "2_2") (pintype "passive"))
      (node (ref "C18") (pin "2") (pinfunction "2_2") (pintype "passive"))
      (node (ref "C19") (pin "2") (pinfunction "2_2") (pintype "passive"))
      (node (ref "C20") (pin "2") (pinfunction "2_2") (pintype "passive"))
      (node (ref "C21") (pin "2") (pinfunction "2_2") (pintype "passive"))
      (node (ref "C22") (pin "2") (pinfunction "2_2") (pintype "passive"))
      (node (ref "C23") (pin "2") (pinfunction "2_2") (pintype "passive"))
      (node (ref "C24") (pin "2") (pinfunction "2_2") (pintype "passive"))
      (node (ref "C25") (pin "2") (pinfunction "2_2") (pintype "passive"))
      (node (ref "C26") (pin "2") (pinfunction "2_2") (pintype "passive"))
      (node (ref "C27") (pin "2") (pinfunction "2_2") (pintype "passive"))
      (node (ref "C29") (pin "2") (pinfunction "2_2") (pintype "passive"))
      (node (ref "C33") (pin "-") (pinfunction "-_-") (pintype "passive"))
      (node (ref "C34") (pin "2") (pinfunction "2_2") (pintype "passive"))
      (node (ref "C37") (pin "1") (pinfunction "1_1") (pintype "passive"))
      (node (ref "C38") (pin "1") (pinfunction "1_1") (pintype "passive"))
      (node (ref "C39") (pin "-") (pinfunction "-_-") (pintype "passive"))
      (node (ref "C40") (pin "-") (pinfunction "-_-") (pintype "passive"))
      (node (ref "C41") (pin "2") (pinfunction "2_2") (pintype "passive"))
      (node (ref "C42") (pin "-") (pinfunction "-_-") (pintype "passive"))
      (node (ref "C5") (pin "1") (pinfunction "1_1") (pintype "passive"))
      (node (ref "C6") (pin "2") (pinfunction "2_2") (pintype "passive"))
      (node (ref "C7") (pin "2") (pinfunction "2_2") (pintype "passive"))
      (node (ref "C8") (pin "2") (pinfunction "2_2") (pintype "passive"))
      (node (ref "C9") (pin "2") (pinfunction "2_2") (pintype "passive"))
      (node (ref "IC1") (pin "11") (pinfunction "GND_11") (pintype "bidirectional"))
      (node (ref "IC2") (pin "4") (pinfunction "GND_4") (pintype "power_in"))
      (node (ref "IC3") (pin "3") (pinfunction "GND_3") (pintype "bidirectional"))
      (node (ref "PWR_HDR") (pin "1") (pinfunction "1_1") (pintype "passive"))
      (node (ref "R17") (pin "1") (pinfunction "1_1") (pintype "passive"))
      (node (ref "R19") (pin "1") (pinfunction "1_1") (pintype "passive"))
      (node (ref "R21") (pin "1") (pinfunction "1_1") (pintype "passive"))
      (node (ref "REG1.2") (pin "1") (pinfunction "GND_1") (pintype "bidirectional"))
      (node (ref "REG2.5") (pin "1") (pinfunction "GND_1") (pintype "bidirectional"))
      (node (ref "SV1") (pin "5") (pinfunction "5_5") (pintype "passive"))
      (node (ref "SV1") (pin "6") (pinfunction "6_6") (pintype "passive"))
      (node (ref "SV2") (pin "2") (pinfunction "2_2") (pintype "passive"))
      (node (ref "SV3") (pin "2") (pinfunction "2_2") (pintype "passive"))
      (node (ref "SV5") (pin "3") (pinfunction "3_3") (pintype "passive"))
      (node (ref "U$1") (pin "GND") (pinfunction "GND_GND") (pintype "bidirectional"))
      (node (ref "U$2") (pin "GND") (pinfunction "GND_GND") (pintype "power_in"))
      (node (ref "U$3") (pin "3") (pinfunction "VSS1_3") (pintype "power_in"))
      (node (ref "U$3") (pin "6") (pinfunction "VSS2_6") (pintype "power_in"))
      (node (ref "U$3") (pin "MT1") (pinfunction "COMMON_SW_MT1") (pintype "passive"))
      (node (ref "U$3") (pin "MT3") (pinfunction "GND_MT3") (pintype "power_in"))
      (node (ref "U$4") (pin "1") (pinfunction "GND_1") (pintype "bidirectional"))
      (node (ref "U$6") (pin "P24") (pinfunction "VSS_P24") (pintype "bidirectional"))
      (node (ref "U$6") (pin "P30") (pinfunction "CE_P30") (pintype "bidirectional"))
      (node (ref "U$7") (pin "GND") (pinfunction "GND_GND") (pintype "bidirectional"))
      (node (ref "U$8") (pin "GND") (pinfunction "GND_GND") (pintype "bidirectional"))
      (node (ref "U$9") (pin "GND") (pinfunction "GND_GND") (pintype "bidirectional"))
      (node (ref "U1") (pin "P101") (pinfunction "GND11_P101") (pintype "passive"))
      (node (ref "U1") (pin "P114") (pinfunction "GND12_P114") (pintype "passive"))
      (node (ref "U1") (pin "P117") (pinfunction "GND13_P117") (pintype "passive"))
      (node (ref "U1") (pin "P136") (pinfunction "GND14_P136") (pintype "passive"))
      (node (ref "U1") (pin "P139") (pinfunction "GND15_P139") (pintype "passive"))
      (node (ref "U1") (pin "P16") (pinfunction "GND1_P16") (pintype "passive"))
      (node (ref "U1") (pin "P22") (pinfunction "GND2_P22") (pintype "passive"))
      (node (ref "U1") (pin "P29") (pinfunction "GND3_P29") (pintype "passive"))
      (node (ref "U1") (pin "P37") (pinfunction "M1_P37") (pintype "bidirectional"))
      (node (ref "U1") (pin "P38") (pinfunction "M0_P38") (pintype "bidirectional"))
      (node (ref "U1") (pin "P39") (pinfunction "M2_P39") (pintype "bidirectional"))
      (node (ref "U1") (pin "P42") (pinfunction "GND4_P42") (pintype "passive"))
      (node (ref "U1") (pin "P45") (pinfunction "GND5_P45") (pintype "passive"))
      (node (ref "U1") (pin "P64") (pinfunction "GND6_P64") (pintype "passive"))
      (node (ref "U1") (pin "P67") (pinfunction "GND7_P67") (pintype "passive"))
      (node (ref "U1") (pin "P81") (pinfunction "GND8_P81") (pintype "passive"))
      (node (ref "U1") (pin "P88") (pinfunction "GND9_P88") (pintype "passive"))
      (node (ref "U1") (pin "P9") (pinfunction "GND0_P9") (pintype "passive"))
      (node (ref "U1") (pin "P94") (pinfunction "GND10_P94") (pintype "passive"))
      (node (ref "X1") (pin "13") (pinfunction "13_13") (pintype "passive"))
      (node (ref "X1") (pin "14") (pinfunction "14_14") (pintype "passive"))
      (node (ref "X1") (pin "17") (pinfunction "17_17") (pintype "passive"))
      (node (ref "X1") (pin "18") (pinfunction "18_18") (pintype "passive"))
      (node (ref "X1") (pin "21") (pinfunction "21_21") (pintype "passive"))
      (node (ref "X1") (pin "4") (pinfunction "4_4") (pintype "passive"))
      (node (ref "X1") (pin "5") (pinfunction "5_5") (pintype "passive"))
      (node (ref "X1") (pin "9") (pinfunction "9_9") (pintype "passive"))
      (node (ref "X3") (pin "3") (pinfunction "3_3") (pintype "passive"))
      (node (ref "X3") (pin "SH1") (pinfunction "PE1_SH1") (pintype "power_in"))
      (node (ref "X3") (pin "SH2") (pinfunction "PE2_SH2") (pintype "power_in"))
      (node (ref "X3") (pin "SH3") (pinfunction "PE3_SH3") (pintype "power_in"))
      (node (ref "X4") (pin "8") (pinfunction "F_8") (pintype "passive"))
      (node (ref "X4") (pin "G1") (pinfunction "G1_G1") (pintype "passive"))
      (node (ref "X5") (pin "8") (pinfunction "F_8") (pintype "passive"))
      (node (ref "X5") (pin "G1") (pinfunction "G1_G1") (pintype "passive"))
      (node (ref "X7") (pin "3") (pinfunction "3_3") (pintype "power_in"))
      (node (ref "X8") (pin "1") (pinfunction "1_1") (pintype "passive"))
    )
    (net (code "92") (name "Net-(C1-Pad2)") (class "Default")
      (node (ref "C1") (pin "2") (pinfunction "2_2") (pintype "passive"))
      (node (ref "R23") (pin "2") (pinfunction "2_2") (pintype "passive"))
      (node (ref "R48") (pin "1") (pinfunction "1_1") (pintype "passive"))
    )
    (net (code "93") (name "Net-(C2-Pad1)") (class "Default")
      (node (ref "C2") (pin "1") (pinfunction "1_1") (pintype "passive"))
      (node (ref "R17") (pin "2") (pinfunction "2_2") (pintype "passive"))
      (node (ref "X8") (pin "2") (pinfunction "2_2") (pintype "passive"))
      (node (ref "X8") (pin "3") (pinfunction "3_3") (pintype "passive"))
      (node (ref "X8") (pin "4") (pinfunction "4_4") (pintype "passive"))
      (node (ref "X8") (pin "5") (pinfunction "5_5") (pintype "passive"))
    )
    (net (code "94") (name "Net-(C3-Pad1)") (class "Default")
      (node (ref "C3") (pin "1") (pinfunction "1_1") (pintype "passive"))
      (node (ref "R48") (pin "2") (pinfunction "2_2") (pintype "passive"))
    )
    (net (code "95") (name "Net-(C4-Pad1)") (class "Default")
      (node (ref "C4") (pin "1") (pinfunction "1_1") (pintype "passive"))
      (node (ref "R49") (pin "2") (pinfunction "2_2") (pintype "passive"))
    )
    (net (code "96") (name "Net-(C5-Pad2)") (class "Default")
      (node (ref "C5") (pin "2") (pinfunction "2_2") (pintype "passive"))
      (node (ref "R34") (pin "2") (pinfunction "2_2") (pintype "passive"))
      (node (ref "R49") (pin "1") (pinfunction "1_1") (pintype "passive"))
    )
    (net (code "97") (name "Net-(C38-Pad2)") (class "Default")
      (node (ref "C38") (pin "2") (pinfunction "2_2") (pintype "passive"))
      (node (ref "JP2") (pin "1") (pinfunction "1_1") (pintype "passive"))
      (node (ref "Q1") (pin "2") (pinfunction "2_2") (pintype "passive"))
    )
    (net (code "98") (name "Net-(IC1-CLK)") (class "Default")
      (node (ref "IC1") (pin "3") (pinfunction "CLK_3") (pintype "bidirectional"))
      (node (ref "U1") (pin "P72") (pinfunction "CCLK_P72") (pintype "bidirectional"))
    )
    (net (code "99") (name "Net-(IC1-TDI)") (class "Default")
      (node (ref "IC1") (pin "4") (pinfunction "TDI_4") (pintype "bidirectional"))
      (node (ref "U1") (pin "P109") (pinfunction "TDO_P109") (pintype "bidirectional"))
    )
    (net (code "100") (name "Net-(IC1-{slash}CE)") (class "Default")
      (node (ref "IC1") (pin "10") (pinfunction "/CE_10") (pintype "bidirectional"))
      (node (ref "U1") (pin "P71") (pinfunction "DONE_P71") (pintype "bidirectional"))
    )
    (net (code "101") (name "Net-(IC1-{slash}CF)") (class "Default")
      (node (ref "IC1") (pin "7") (pinfunction "/CF_7") (pintype "bidirectional"))
      (node (ref "U1") (pin "P143") (pinfunction "PROG_B_P143") (pintype "bidirectional"))
    )
    (net (code "102") (name "Net-(IC3-D+)") (class "Default")
      (node (ref "IC3") (pin "29") (pinfunction "D+_29") (pintype "bidirectional"))
      (node (ref "R54") (pin "2") (pinfunction "2_2") (pintype "passive"))
    )
    (net (code "103") (name "Net-(IC3-D-)") (class "Default")
      (node (ref "IC3") (pin "30") (pinfunction "D-_30") (pintype "bidirectional"))
      (node (ref "R53") (pin "2") (pinfunction "2_2") (pintype "passive"))
    )
    (net (code "104") (name "Net-(IC3-UCAP)") (class "Default")
      (node (ref "C41") (pin "1") (pinfunction "1_1") (pintype "passive"))
      (node (ref "IC3") (pin "27") (pinfunction "UCAP_27") (pintype "bidirectional"))
    )
    (net (code "105") (name "Net-(IC3-UGND)") (class "Default")
      (node (ref "IC3") (pin "28") (pinfunction "UGND_28") (pintype "bidirectional"))
      (node (ref "X6") (pin "4") (pinfunction "4_4") (pintype "passive"))
    )
    (net (code "106") (name "Net-(IC3-XTAL1)") (class "Default")
      (node (ref "IC3") (pin "1") (pinfunction "XTAL1_1") (pintype "bidirectional"))
      (node (ref "JP2") (pin "2") (pinfunction "2_2") (pintype "passive"))
    )
    (net (code "107") (name "Net-(IC3-XTAL2{slash}PC0)") (class "Default")
      (node (ref "C37") (pin "2") (pinfunction "2_2") (pintype "passive"))
      (node (ref "IC3") (pin "2") (pinfunction "XTAL2/PC0_2") (pintype "bidirectional"))
      (node (ref "Q1") (pin "1") (pinfunction "1_1") (pintype "passive"))
    )
    (net (code "108") (name "Net-(Q5-B)") (class "Default")
      (node (ref "Q5") (pin "1") (pinfunction "B_1") (pintype "passive"))
      (node (ref "R8") (pin "2") (pinfunction "2_2") (pintype "passive"))
    )
    (net (code "109") (name "Net-(Q5-E)") (class "Default")
      (node (ref "Q5") (pin "2") (pinfunction "E_2") (pintype "passive"))
      (node (ref "R13") (pin "2") (pinfunction "2_2") (pintype "passive"))
      (node (ref "R14") (pin "2") (pinfunction "2_2") (pintype "passive"))
    )
    (net (code "110") (name "Net-(Q6-B)") (class "Default")
      (node (ref "Q6") (pin "1") (pinfunction "B_1") (pintype "passive"))
      (node (ref "R10") (pin "2") (pinfunction "2_2") (pintype "passive"))
      (node (ref "R9") (pin "2") (pinfunction "2_2") (pintype "passive"))
    )
    (net (code "111") (name "Net-(Q6-E)") (class "Default")
      (node (ref "Q6") (pin "2") (pinfunction "E_2") (pintype "passive"))
      (node (ref "R15") (pin "2") (pinfunction "2_2") (pintype "passive"))
      (node (ref "R16") (pin "2") (pinfunction "2_2") (pintype "passive"))
      (node (ref "R20") (pin "2") (pinfunction "2_2") (pintype "passive"))
    )
    (net (code "112") (name "Net-(Q7-B)") (class "Default")
      (node (ref "Q7") (pin "1") (pinfunction "B_1") (pintype "passive"))
      (node (ref "R29") (pin "2") (pinfunction "2_2") (pintype "passive"))
      (node (ref "R30") (pin "2") (pinfunction "2_2") (pintype "passive"))
    )
    (net (code "113") (name "Net-(Q7-E)") (class "Default")
      (node (ref "Q7") (pin "2") (pinfunction "E_2") (pintype "passive"))
      (node (ref "R31") (pin "2") (pinfunction "2_2") (pintype "passive"))
      (node (ref "R32") (pin "2") (pinfunction "2_2") (pintype "passive"))
      (node (ref "R33") (pin "2") (pinfunction "2_2") (pintype "passive"))
    )
    (net (code "114") (name "Net-(Q8-B)") (class "Default")
      (node (ref "Q8") (pin "1") (pinfunction "B_1") (pintype "passive"))
      (node (ref "R24") (pin "2") (pinfunction "2_2") (pintype "passive"))
      (node (ref "R25") (pin "2") (pinfunction "2_2") (pintype "passive"))
    )
    (net (code "115") (name "Net-(Q8-E)") (class "Default")
      (node (ref "Q8") (pin "2") (pinfunction "E_2") (pintype "passive"))
      (node (ref "R26") (pin "2") (pinfunction "2_2") (pintype "passive"))
      (node (ref "R27") (pin "2") (pinfunction "2_2") (pintype "passive"))
      (node (ref "R28") (pin "2") (pinfunction "2_2") (pintype "passive"))
    )
    (net (code "116") (name "Net-(R18-Pad2)") (class "Default")
      (node (ref "R18") (pin "2") (pinfunction "2_2") (pintype "passive"))
      (node (ref "R22") (pin "2") (pinfunction "2_2") (pintype "passive"))
    )
    (net (code "117") (name "Net-(R53-Pad1)") (class "Default")
      (node (ref "R53") (pin "1") (pinfunction "1_1") (pintype "passive"))
      (node (ref "X6") (pin "2") (pinfunction "2_2") (pintype "passive"))
    )
    (net (code "118") (name "Net-(R54-Pad1)") (class "Default")
      (node (ref "R54") (pin "1") (pinfunction "1_1") (pintype "passive"))
      (node (ref "X6") (pin "3") (pinfunction "3_3") (pintype "passive"))
    )
    (net (code "119") (name "Net-(T2-B)") (class "Default")
      (node (ref "C2") (pin "2") (pinfunction "2_2") (pintype "passive"))
      (node (ref "R18") (pin "1") (pinfunction "1_1") (pintype "passive"))
      (node (ref "R19") (pin "2") (pinfunction "2_2") (pintype "passive"))
      (node (ref "T2") (pin "1") (pinfunction "B_1") (pintype "passive"))
    )
    (net (code "120") (name "Net-(U$6-A0)") (class "Default")
      (node (ref "U$6") (pin "P20") (pinfunction "A0_P20") (pintype "bidirectional"))
      (node (ref "U1") (pin "P24") (pinfunction "IO_L24N_6VREF_6_P24") (pintype "bidirectional"))
    )
    (net (code "121") (name "Net-(U$6-A1)") (class "Default")
      (node (ref "U$6") (pin "P19") (pinfunction "A1_P19") (pintype "bidirectional"))
      (node (ref "U1") (pin "P23") (pinfunction "IO_L24P_6_P23") (pintype "bidirectional"))
    )
    (net (code "122") (name "Net-(U$6-A2)") (class "Default")
      (node (ref "U$6") (pin "P18") (pinfunction "A2_P18") (pintype "bidirectional"))
      (node (ref "U1") (pin "P21") (pinfunction "IO_L40N_6_P21") (pintype "bidirectional"))
    )
    (net (code "123") (name "Net-(U$6-A3)") (class "Default")
      (node (ref "U$6") (pin "P17") (pinfunction "A3_P17") (pintype "bidirectional"))
      (node (ref "U1") (pin "P20") (pinfunction "IO_L40P_6VREF_6_P20") (pintype "bidirectional"))
    )
    (net (code "124") (name "Net-(U$6-A4)") (class "Default")
      (node (ref "U$6") (pin "P16") (pinfunction "A4_P16") (pintype "bidirectional"))
      (node (ref "U1") (pin "P18") (pinfunction "IO_L40N_7VREF_7_P18") (pintype "bidirectional"))
    )
    (net (code "125") (name "Net-(U$6-A5)") (class "Default")
      (node (ref "U$6") (pin "P15") (pinfunction "A5_P15") (pintype "bidirectional"))
      (node (ref "U1") (pin "P17") (pinfunction "IO_L40P_7_P17") (pintype "bidirectional"))
    )
    (net (code "126") (name "Net-(U$6-A6)") (class "Default")
      (node (ref "U$6") (pin "P14") (pinfunction "A6_P14") (pintype "bidirectional"))
      (node (ref "U1") (pin "P15") (pinfunction "IO_L24N_7_P15") (pintype "bidirectional"))
    )
    (net (code "127") (name "Net-(U$6-A7)") (class "Default")
      (node (ref "U$6") (pin "P13") (pinfunction "A7_P13") (pintype "bidirectional"))
      (node (ref "U1") (pin "P14") (pinfunction "IO_L24P_7_P14") (pintype "bidirectional"))
    )
    (net (code "128") (name "Net-(U$6-A8)") (class "Default")
      (node (ref "U$6") (pin "P3") (pinfunction "A8_P3") (pintype "bidirectional"))
      (node (ref "U1") (pin "P4") (pinfunction "IOVREF_7_P4") (pintype "bidirectional"))
    )
    (net (code "129") (name "Net-(U$6-A9)") (class "Default")
      (node (ref "U$6") (pin "P2") (pinfunction "A9_P2") (pintype "bidirectional"))
      (node (ref "U1") (pin "P2") (pinfunction "IO_L01N_7VRP_7_P2") (pintype "bidirectional"))
    )
    (net (code "130") (name "Net-(U$6-A10)") (class "Default")
      (node (ref "U$6") (pin "P31") (pinfunction "A10_P31") (pintype "bidirectional"))
      (node (ref "U1") (pin "P35") (pinfunction "IO_L01P_6VRN_6_P35") (pintype "bidirectional"))
    )
    (net (code "131") (name "Net-(U$6-A11)") (class "Default")
      (node (ref "U$6") (pin "P1") (pinfunction "A11_P1") (pintype "bidirectional"))
      (node (ref "U1") (pin "P1") (pinfunction "IO_L01P_7VRN_7_P1") (pintype "bidirectional"))
    )
    (net (code "132") (name "Net-(U$6-A12)") (class "Default")
      (node (ref "U$6") (pin "P12") (pinfunction "A12_P12") (pintype "bidirectional"))
      (node (ref "U1") (pin "P13") (pinfunction "IO_L23N_7_P13") (pintype "bidirectional"))
    )
    (net (code "133") (name "Net-(U$6-A13)") (class "Default")
      (node (ref "U$6") (pin "P4") (pinfunction "A13_P4") (pintype "bidirectional"))
      (node (ref "U1") (pin "P5") (pinfunction "IO_L20P_7_P5") (pintype "bidirectional"))
    )
    (net (code "134") (name "Net-(U$6-A14)") (class "Default")
      (node (ref "U$6") (pin "P11") (pinfunction "A14_P11") (pintype "bidirectional"))
      (node (ref "U1") (pin "P12") (pinfunction "IO_L23P_7_P12") (pintype "bidirectional"))
    )
    (net (code "135") (name "Net-(U$6-A15)") (class "Default")
      (node (ref "U$6") (pin "P7") (pinfunction "A15_P7") (pintype "bidirectional"))
      (node (ref "U1") (pin "P8") (pinfunction "IO_L21N_7_P8") (pintype "bidirectional"))
    )
    (net (code "136") (name "Net-(U$6-A16)") (class "Default")
      (node (ref "U$6") (pin "P10") (pinfunction "A16_P10") (pintype "bidirectional"))
      (node (ref "U1") (pin "P11") (pinfunction "IO_L22N_7_P11") (pintype "bidirectional"))
    )
    (net (code "137") (name "Net-(U$6-A17)") (class "Default")
      (node (ref "U$6") (pin "P6") (pinfunction "A17_P6") (pintype "bidirectional"))
      (node (ref "U1") (pin "P7") (pinfunction "IO_L21P_7_P7") (pintype "bidirectional"))
    )
    (net (code "138") (name "Net-(U$6-A18)") (class "Default")
      (node (ref "U$6") (pin "P9") (pinfunction "A18_P9") (pintype "bidirectional"))
      (node (ref "U1") (pin "P10") (pinfunction "IO_L22P_7_P10") (pintype "bidirectional"))
    )
    (net (code "139") (name "Net-(U$6-DQ0)") (class "Default")
      (node (ref "U$6") (pin "P21") (pinfunction "DQ0_P21") (pintype "bidirectional"))
      (node (ref "U1") (pin "P25") (pinfunction "IO_L23P_6_P25") (pintype "bidirectional"))
    )
    (net (code "140") (name "Net-(U$6-DQ1)") (class "Default")
      (node (ref "U$6") (pin "P22") (pinfunction "DQ1_P22") (pintype "bidirectional"))
      (node (ref "U1") (pin "P26") (pinfunction "IO_L23N_6_P26") (pintype "bidirectional"))
    )
    (net (code "141") (name "Net-(U$6-DQ2)") (class "Default")
      (node (ref "U$6") (pin "P23") (pinfunction "DQ2_P23") (pintype "bidirectional"))
      (node (ref "U1") (pin "P27") (pinfunction "IO_L22P_6_P27") (pintype "bidirectional"))
    )
    (net (code "142") (name "Net-(U$6-DQ3)") (class "Default")
      (node (ref "U$6") (pin "P25") (pinfunction "DQ3_P25") (pintype "bidirectional"))
      (node (ref "U1") (pin "P28") (pinfunction "IO_L22N_6_P28") (pintype "bidirectional"))
    )
    (net (code "143") (name "Net-(U$6-DQ4)") (class "Default")
      (node (ref "U$6") (pin "P26") (pinfunction "DQ4_P26") (pintype "bidirectional"))
      (node (ref "U1") (pin "P30") (pinfunction "IO_L21P_6_P30") (pintype "bidirectional"))
    )
    (net (code "144") (name "Net-(U$6-DQ5)") (class "Default")
      (node (ref "U$6") (pin "P27") (pinfunction "DQ5_P27") (pintype "bidirectional"))
      (node (ref "U1") (pin "P31") (pinfunction "IO_L21N_6_P31") (pintype "bidirectional"))
    )
    (net (code "145") (name "Net-(U$6-DQ6)") (class "Default")
      (node (ref "U$6") (pin "P28") (pinfunction "DQ6_P28") (pintype "bidirectional"))
      (node (ref "U1") (pin "P32") (pinfunction "IO_L20P_6_P32") (pintype "bidirectional"))
    )
    (net (code "146") (name "Net-(U$6-DQ7)") (class "Default")
      (node (ref "U$6") (pin "P29") (pinfunction "DQ7_P29") (pintype "bidirectional"))
      (node (ref "U1") (pin "P33") (pinfunction "IO_L20N_6_P33") (pintype "bidirectional"))
    )
    (net (code "147") (name "Net-(U$6-OE)") (class "Default")
      (node (ref "U$6") (pin "P32") (pinfunction "OE_P32") (pintype "bidirectional"))
      (node (ref "U1") (pin "P36") (pinfunction "IO_L01N_6VRP_6_P36") (pintype "bidirectional"))
    )
    (net (code "148") (name "Net-(U$6-WE)") (class "Default")
      (node (ref "U$6") (pin "P5") (pinfunction "WE_P5") (pintype "bidirectional"))
      (node (ref "U1") (pin "P6") (pinfunction "IO_L20N_7_P6") (pintype "bidirectional"))
    )
    (net (code "149") (name "Net-(U1A-IO_L27N_0)") (class "Default")
      (node (ref "SV3") (pin "3") (pinfunction "3_3") (pintype "passive"))
      (node (ref "U1") (pin "P137") (pinfunction "IO_L27N_0_P137") (pintype "bidirectional"))
    )
    (net (code "150") (name "Net-(U1A-IO_L27P_0)") (class "Default")
      (node (ref "SV3") (pin "4") (pinfunction "4_4") (pintype "passive"))
      (node (ref "U1") (pin "P135") (pinfunction "IO_L27P_0_P135") (pintype "bidirectional"))
    )
    (net (code "151") (name "Net-(U1A-IO_L30N_0)") (class "Default")
      (node (ref "SV3") (pin "5") (pinfunction "5_5") (pintype "passive"))
      (node (ref "U1") (pin "P132") (pinfunction "IO_L30N_0_P132") (pintype "bidirectional"))
    )
    (net (code "152") (name "Net-(U1A-IO_L31N_0)") (class "Default")
      (node (ref "SV3") (pin "6") (pinfunction "6_6") (pintype "passive"))
      (node (ref "U1") (pin "P130") (pinfunction "IO_L31N_0_P130") (pintype "bidirectional"))
    )
    (net (code "153") (name "Net-(U1A-IO_L31P_0VREF_0)") (class "Default")
      (node (ref "SV3") (pin "7") (pinfunction "7_7") (pintype "passive"))
      (node (ref "U1") (pin "P129") (pinfunction "IO_L31P_0VREF_0_P129") (pintype "bidirectional"))
    )
    (net (code "154") (name "Net-(U1A-IO_L32N_0GCLK7)") (class "Default")
      (node (ref "SV3") (pin "8") (pinfunction "8_8") (pintype "passive"))
      (node (ref "U1") (pin "P128") (pinfunction "IO_L32N_0GCLK7_P128") (pintype "bidirectional"))
    )
    (net (code "155") (name "Net-(U1A-IO_L32P_0GCLK6)") (class "Default")
      (node (ref "SV3") (pin "9") (pinfunction "9_9") (pintype "passive"))
      (node (ref "U1") (pin "P127") (pinfunction "IO_L32P_0GCLK6_P127") (pintype "bidirectional"))
    )
    (net (code "156") (name "Net-(U1C-IO_L31N_1VREF_1)") (class "Default")
      (node (ref "SV3") (pin "10") (pinfunction "10_10") (pintype "passive"))
      (node (ref "U1") (pin "P123") (pinfunction "IO_L31N_1VREF_1_P123") (pintype "bidirectional"))
    )
    (net (code "157") (name "Net-(U1N-TCK)") (class "Default")
      (node (ref "R2") (pin "1") (pinfunction "1_1") (pintype "passive"))
      (node (ref "U1") (pin "P110") (pinfunction "TCK_P110") (pintype "bidirectional"))
    )
    (net (code "158") (name "Net-(U1N-TDI)") (class "Default")
      (node (ref "R1") (pin "1") (pinfunction "1_1") (pintype "passive"))
      (node (ref "U1") (pin "P144") (pinfunction "TDI_P144") (pintype "bidirectional"))
    )
    (net (code "159") (name "Net-(U1N-TMS)") (class "Default")
      (node (ref "R3") (pin "1") (pinfunction "1_1") (pintype "passive"))
      (node (ref "U1") (pin "P111") (pinfunction "TMS_P111") (pintype "bidirectional"))
    )
    (net (code "160") (name "unconnected-(IC1-NC.1-Pad2)") (class "Default")
      (node (ref "IC1") (pin "2") (pinfunction "NC.1_2") (pintype "bidirectional"))
    )
    (net (code "161") (name "unconnected-(IC1-NC.2-Pad9)") (class "Default")
      (node (ref "IC1") (pin "9") (pinfunction "NC.2_9") (pintype "bidirectional"))
    )
    (net (code "162") (name "unconnected-(IC1-NC.3-Pad12)") (class "Default")
      (node (ref "IC1") (pin "12") (pinfunction "NC.3_12") (pintype "bidirectional"))
    )
    (net (code "163") (name "unconnected-(IC1-NC.4-Pad14)") (class "Default")
      (node (ref "IC1") (pin "14") (pinfunction "NC.4_14") (pintype "bidirectional"))
    )
    (net (code "164") (name "unconnected-(IC1-NC.5-Pad15)") (class "Default")
      (node (ref "IC1") (pin "15") (pinfunction "NC.5_15") (pintype "bidirectional"))
    )
    (net (code "165") (name "unconnected-(IC1-NC.6-Pad16)") (class "Default")
      (node (ref "IC1") (pin "16") (pinfunction "NC.6_16") (pintype "bidirectional"))
    )
    (net (code "166") (name "unconnected-(IC1-{slash}CEO-Pad13)") (class "Default")
      (node (ref "IC1") (pin "13") (pinfunction "/CEO_13") (pintype "bidirectional"))
    )
    (net (code "167") (name "unconnected-(REG1.2-VOUT2-Pad2)") (class "Default")
      (node (ref "REG1.2") (pin "2") (pinfunction "VOUT2_2") (pintype "bidirectional"))
    )
    (net (code "168") (name "unconnected-(REG2.5-VOUT2-Pad2)") (class "Default")
      (node (ref "REG2.5") (pin "2") (pinfunction "VOUT2_2") (pintype "bidirectional"))
    )
    (net (code "169") (name "unconnected-(U$2-TRI-PadENA)") (class "Default")
      (node (ref "U$2") (pin "ENA") (pinfunction "TRI_ENA") (pintype "input"))
    )
    (net (code "170") (name "unconnected-(U$3-CARD_DETECT-PadCD)") (class "Default")
      (node (ref "U$3") (pin "CD") (pinfunction "CARD_DETECT_CD") (pintype "passive"))
    )
    (net (code "171") (name "unconnected-(U$3-DAT1-Pad8)") (class "Default")
      (node (ref "U$3") (pin "8") (pinfunction "DAT1_8") (pintype "bidirectional"))
    )
    (net (code "172") (name "unconnected-(U$3-DAT2-Pad9)") (class "Default")
      (node (ref "U$3") (pin "9") (pinfunction "DAT2_9") (pintype "bidirectional"))
    )
    (net (code "173") (name "unconnected-(U$3-WRITE_PROTECT-PadWP)") (class "Default")
      (node (ref "U$3") (pin "WP") (pinfunction "WRITE_PROTECT_WP") (pintype "passive"))
    )
    (net (code "174") (name "unconnected-(U$4-VOUT2-Pad2)") (class "Default")
      (node (ref "U$4") (pin "2") (pinfunction "VOUT2_2") (pintype "bidirectional"))
    )
    (net (code "175") (name "unconnected-(U1N-HSWAP_EN-PadP142)") (class "Default")
      (node (ref "U1") (pin "P142") (pinfunction "HSWAP_EN_P142") (pintype "bidirectional"))
    )
    (net (code "176") (name "unconnected-(X1-Pad10)") (class "Default")
      (node (ref "X1") (pin "10") (pinfunction "10_10") (pintype "passive"))
    )
    (net (code "177") (name "unconnected-(X1-Pad12)") (class "Default")
      (node (ref "X1") (pin "12") (pinfunction "12_12") (pintype "passive"))
    )
    (net (code "178") (name "unconnected-(X3-Pad2)") (class "Default")
      (node (ref "X3") (pin "2") (pinfunction "2_2") (pintype "passive"))
    )
    (net (code "179") (name "unconnected-(X3-Pad8)") (class "Default")
      (node (ref "X3") (pin "8") (pinfunction "8_8") (pintype "passive"))
    )
    (net (code "180") (name "unconnected-(X4-PadG2)") (class "Default")
      (node (ref "X4") (pin "G2") (pinfunction "G2_G2") (pintype "passive"))
    )
    (net (code "181") (name "unconnected-(X5-PadG2)") (class "Default")
      (node (ref "X5") (pin "G2") (pinfunction "G2_G2") (pintype "passive"))
    )
    (net (code "182") (name "unconnected-(X6-Pad1)") (class "Default")
      (node (ref "X6") (pin "1") (pinfunction "1_1") (pintype "passive"))
    )
  )
)
